# Radio.net
KiCad netlist of a schematic drawn in EAGLE
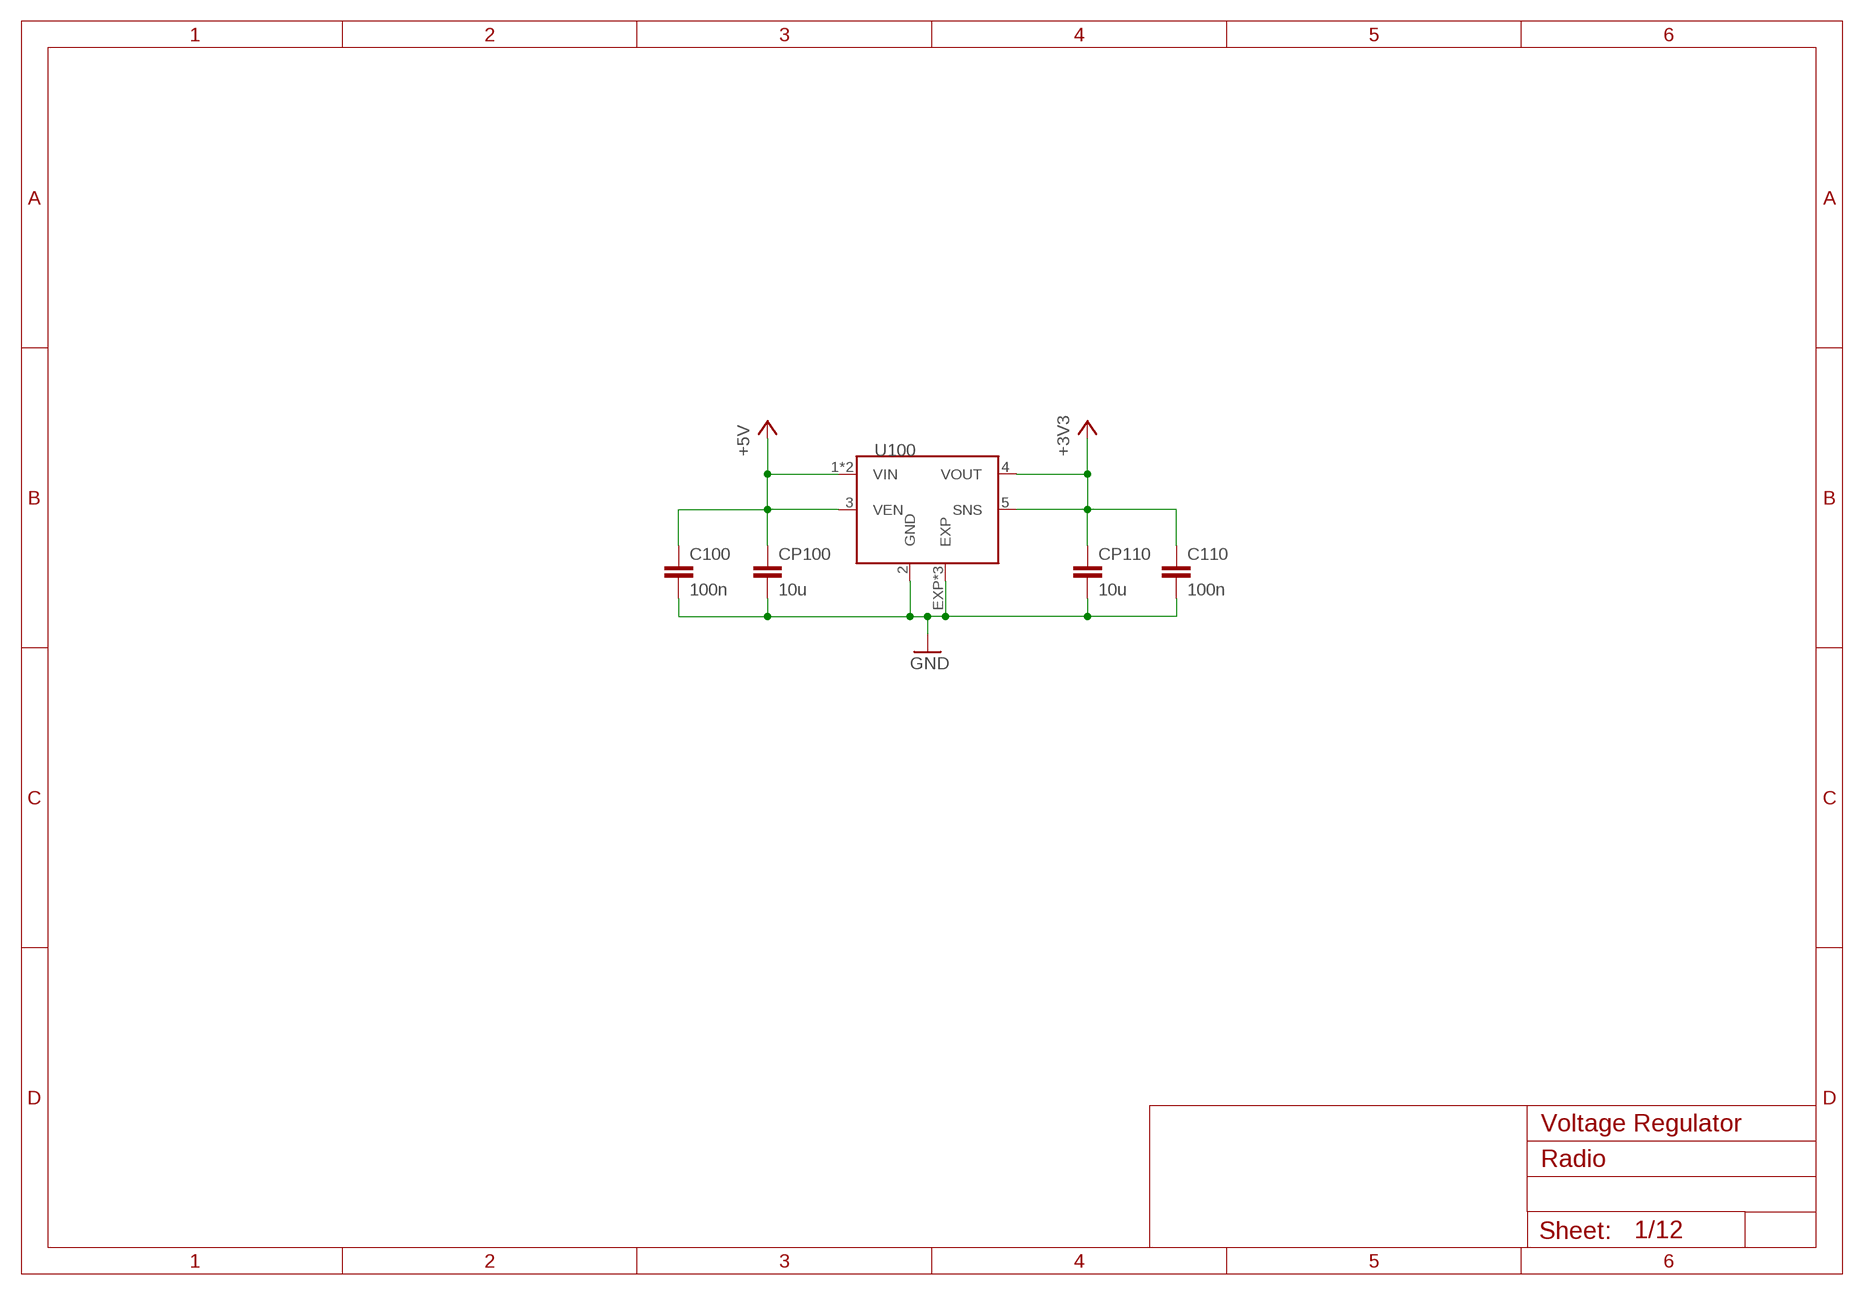
[diagram p0: schematic, sheet 1]
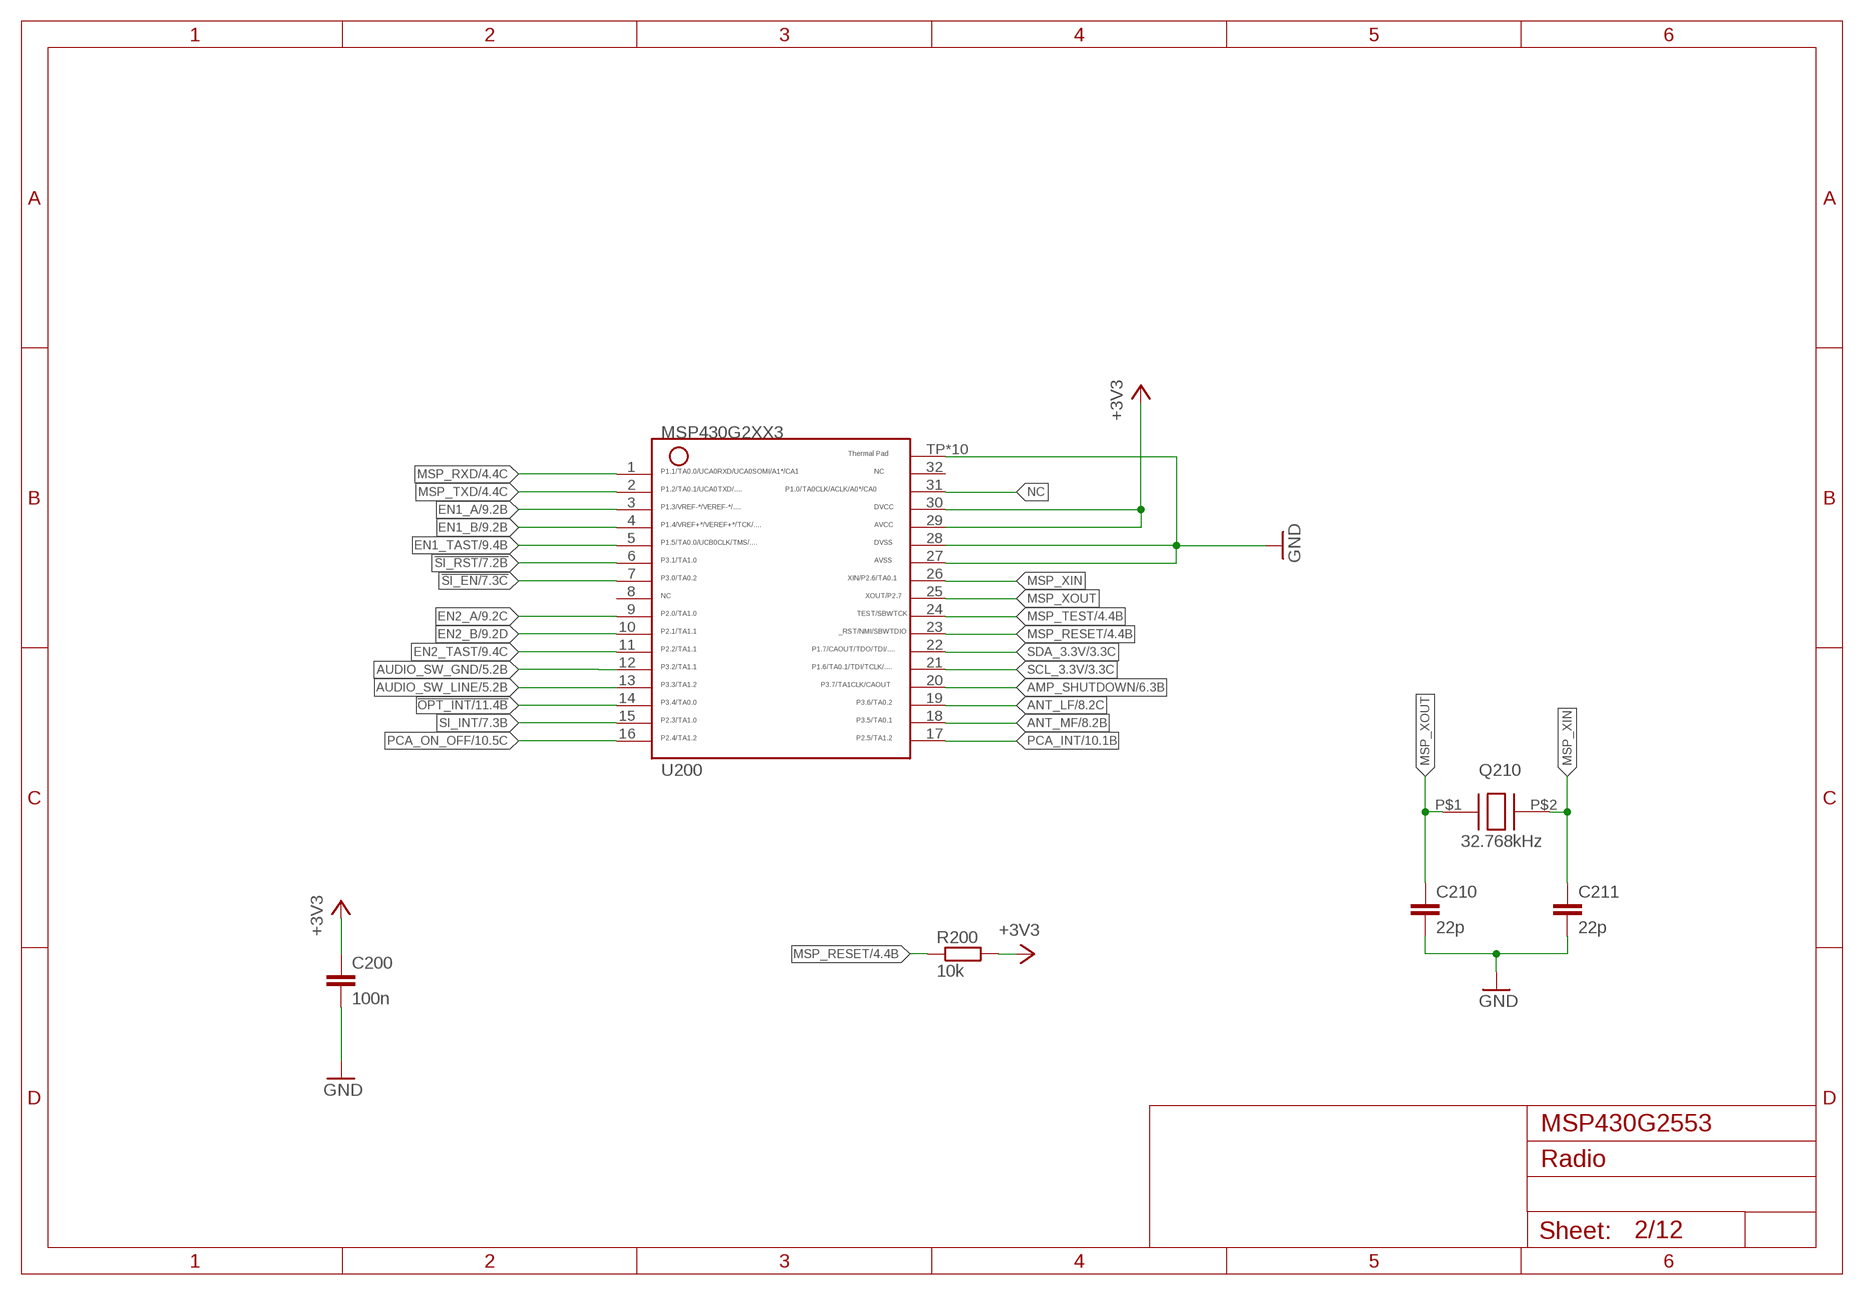
[diagram p1: schematic, sheet 2]
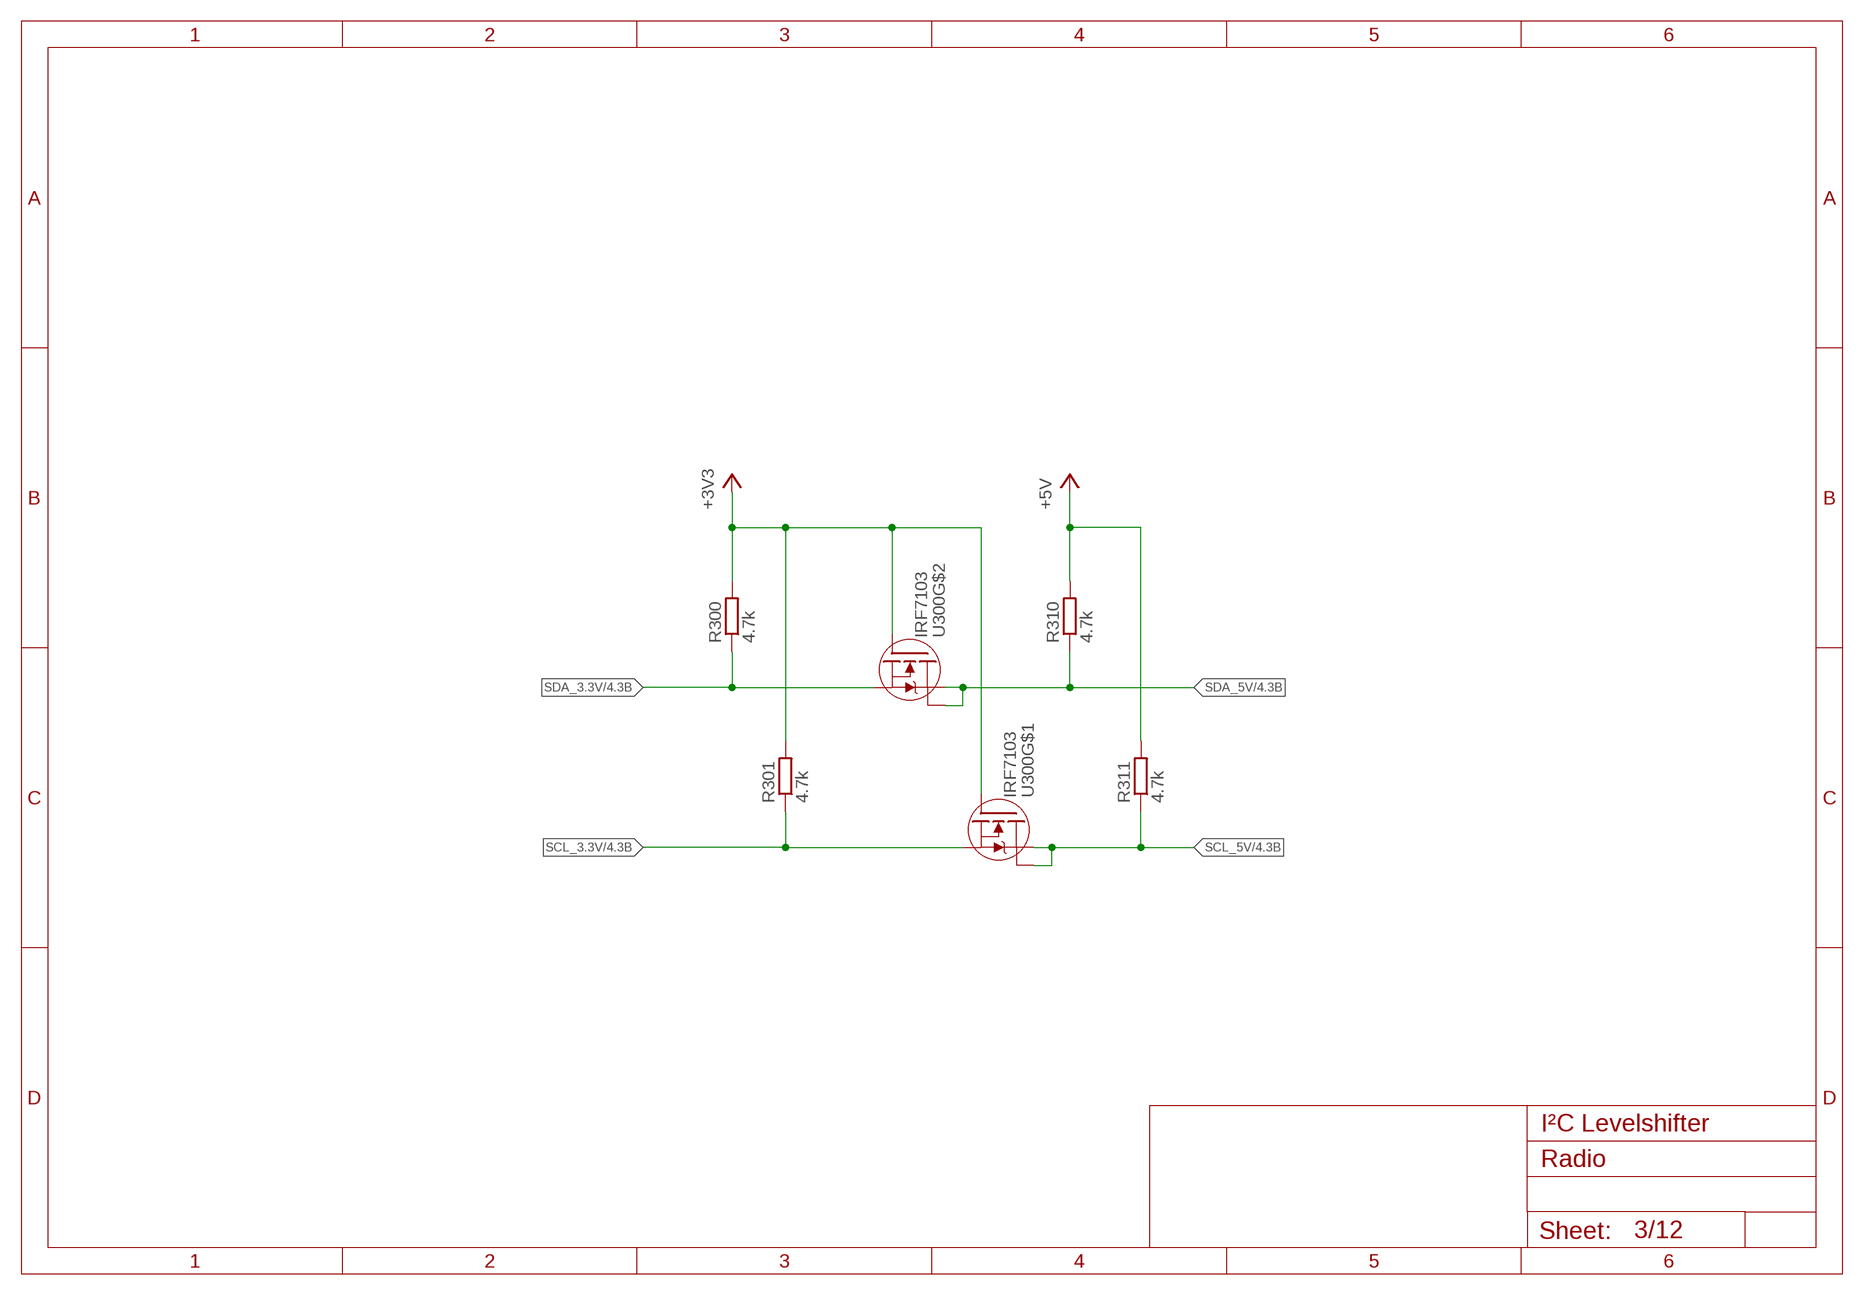
[diagram p2: schematic, sheet 3]
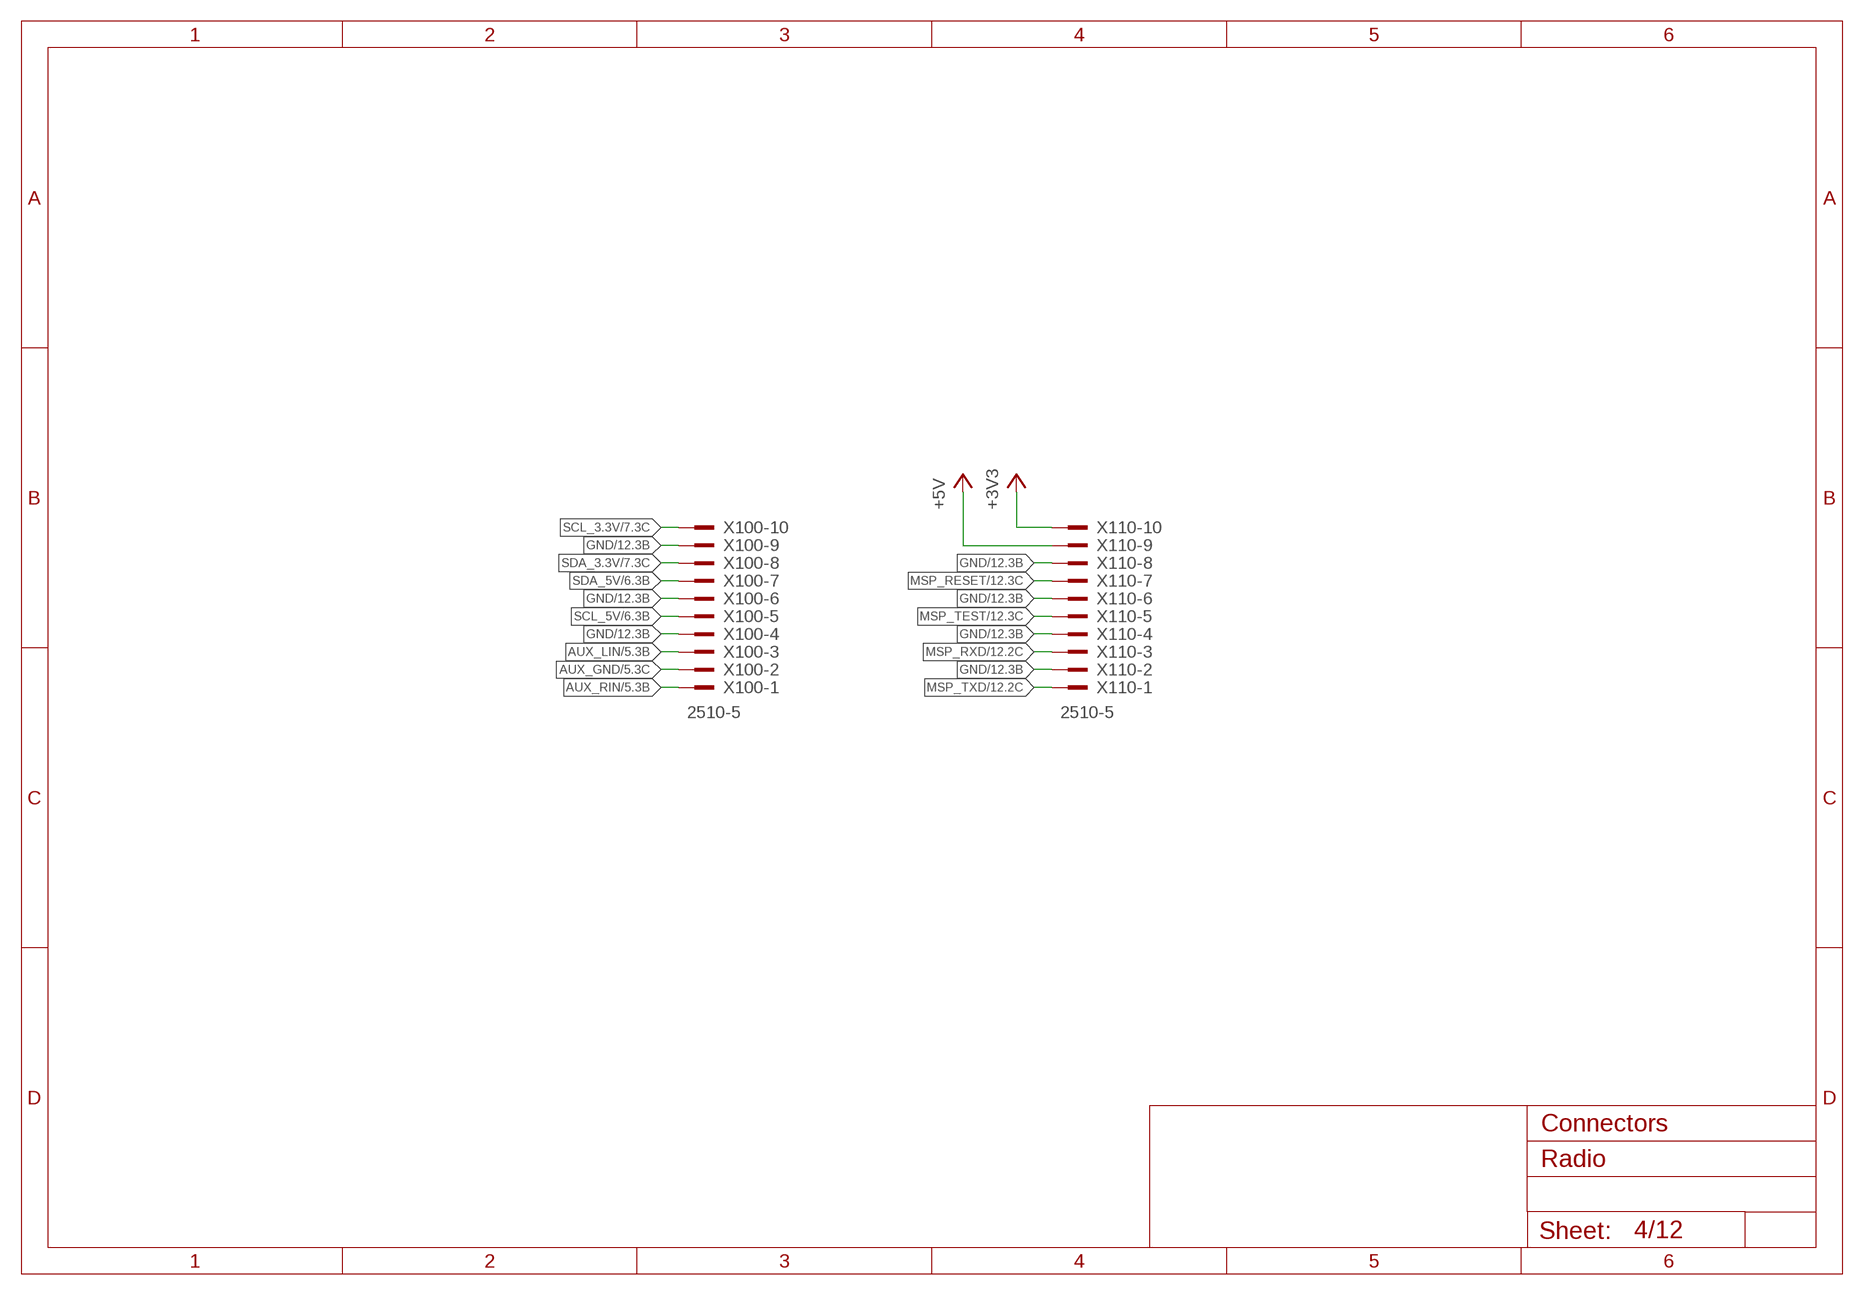
[diagram p3: schematic, sheet 4]
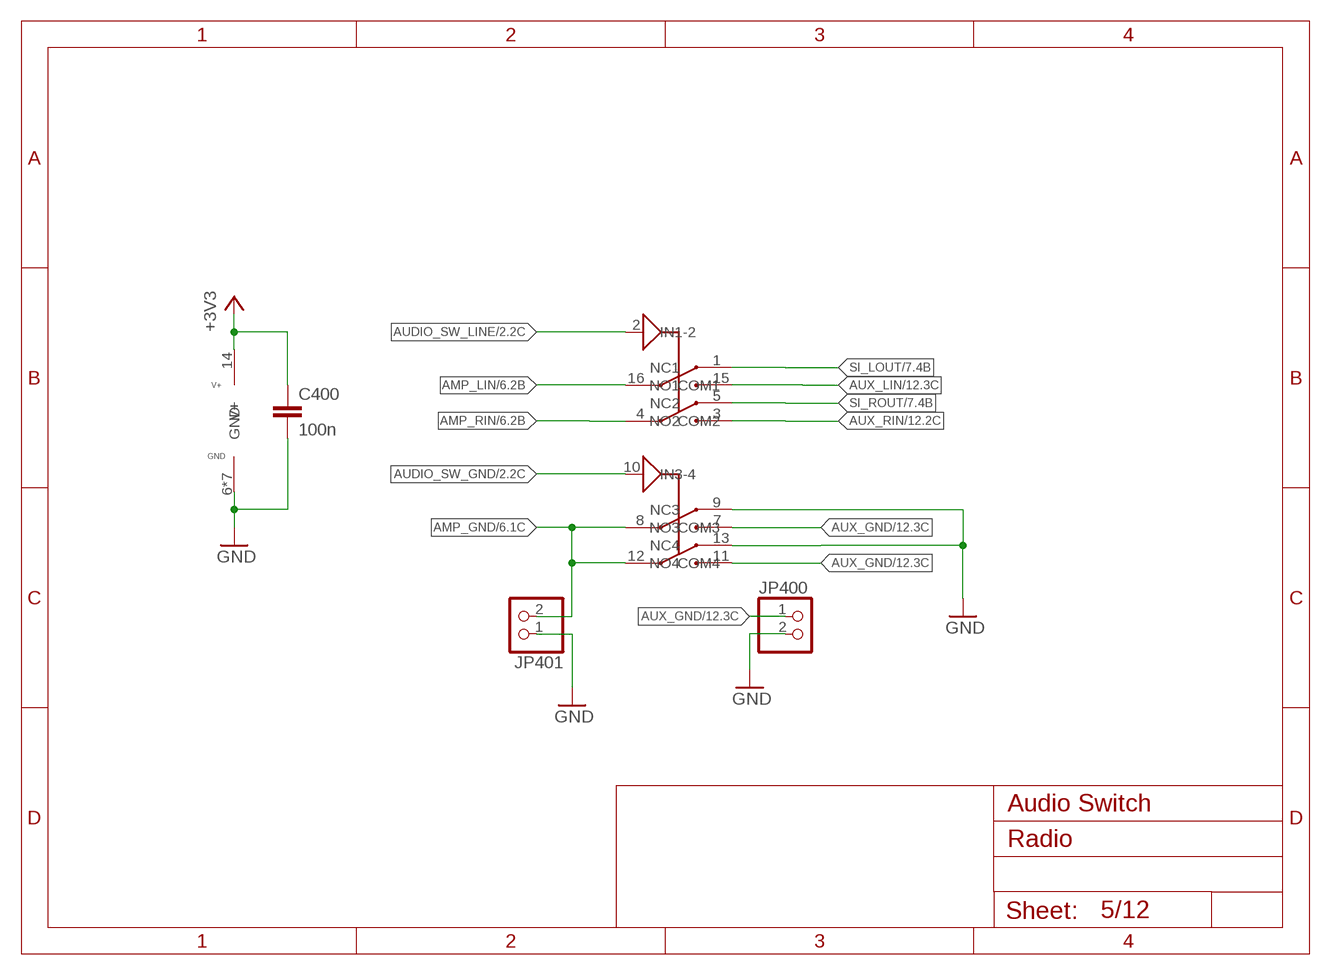
[diagram p4: schematic, sheet 5]
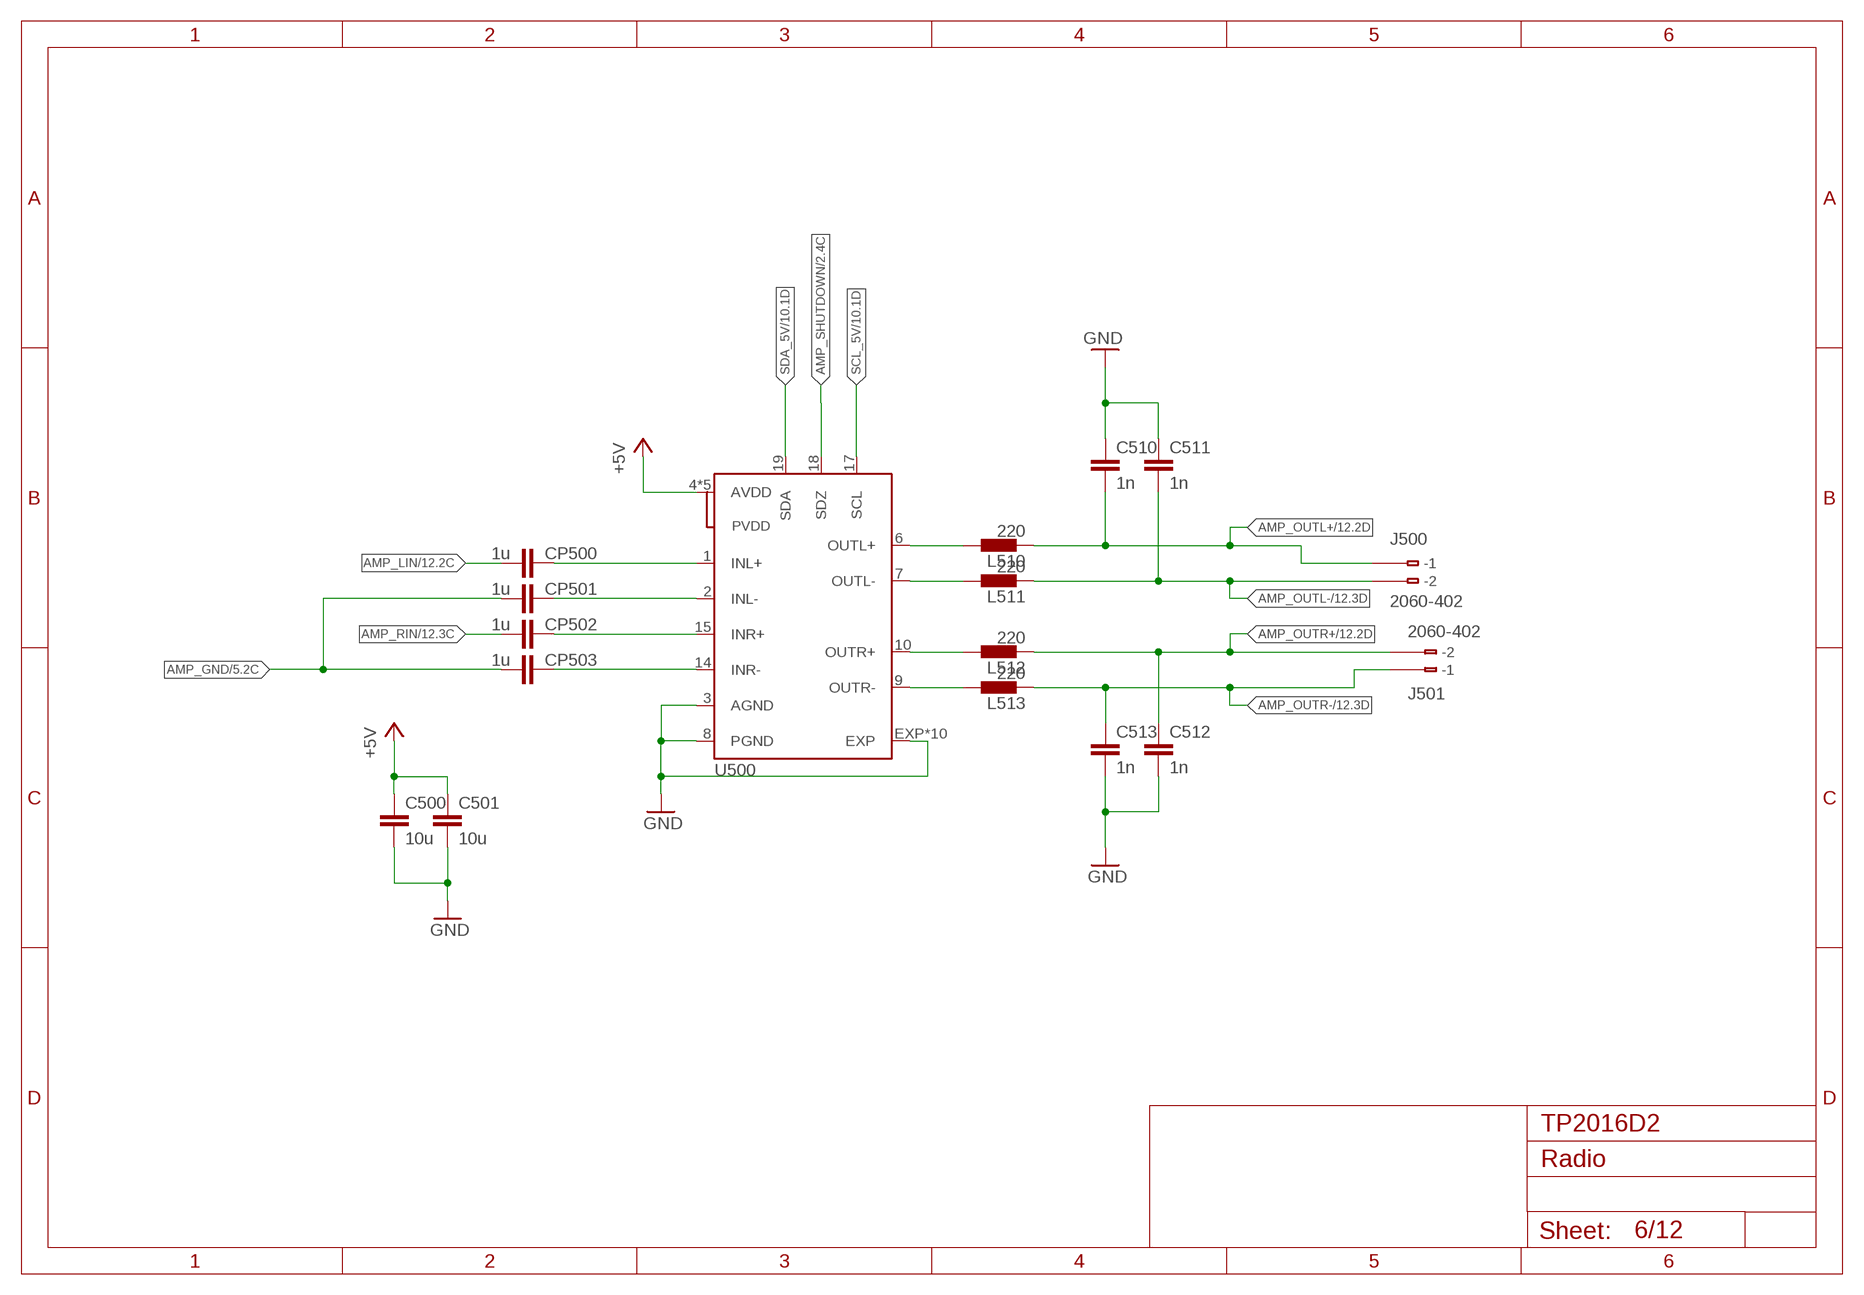
[diagram p5: schematic, sheet 6]
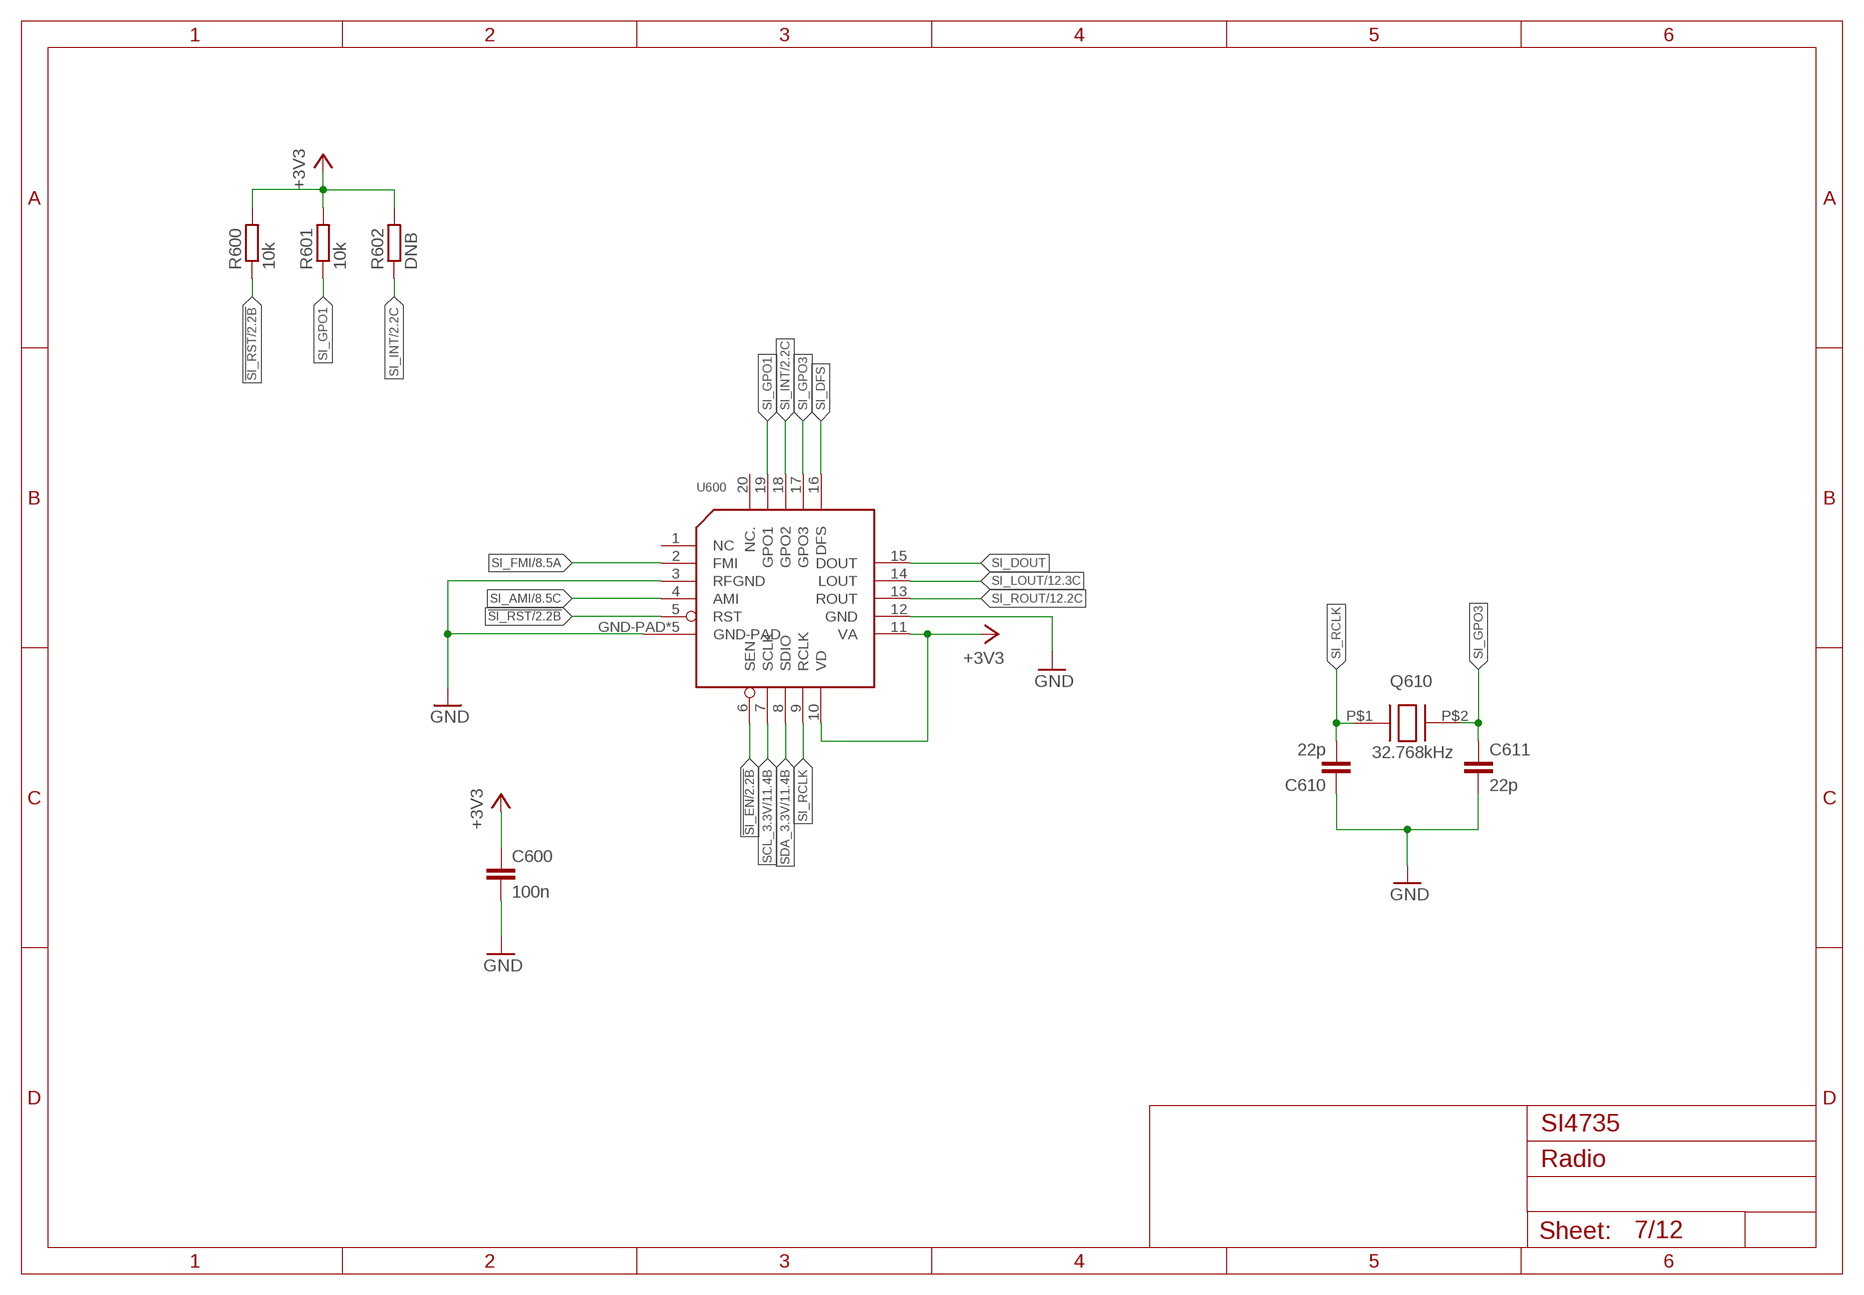
[diagram p6: schematic, sheet 7]
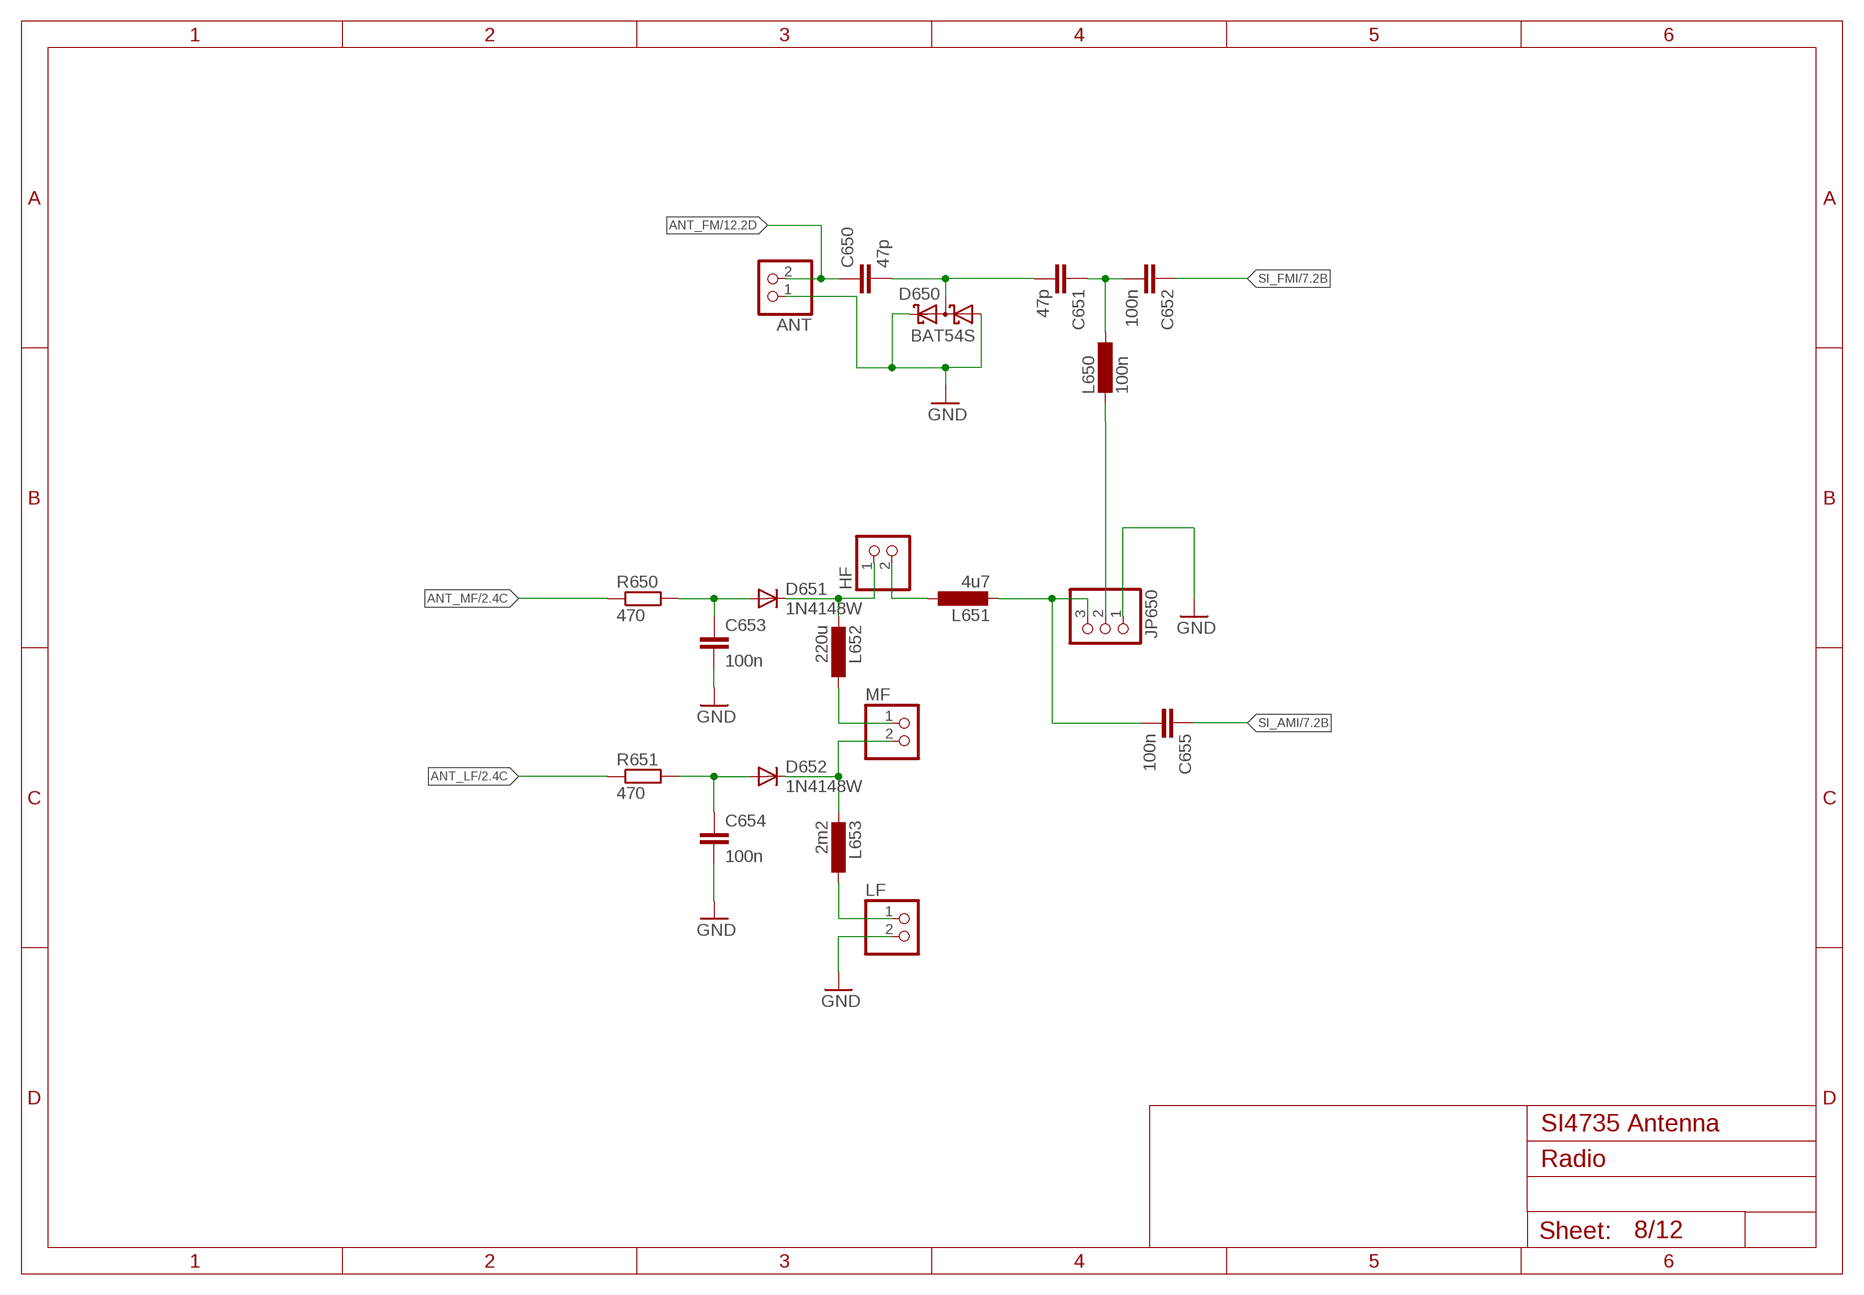
[diagram p7: schematic, sheet 8]
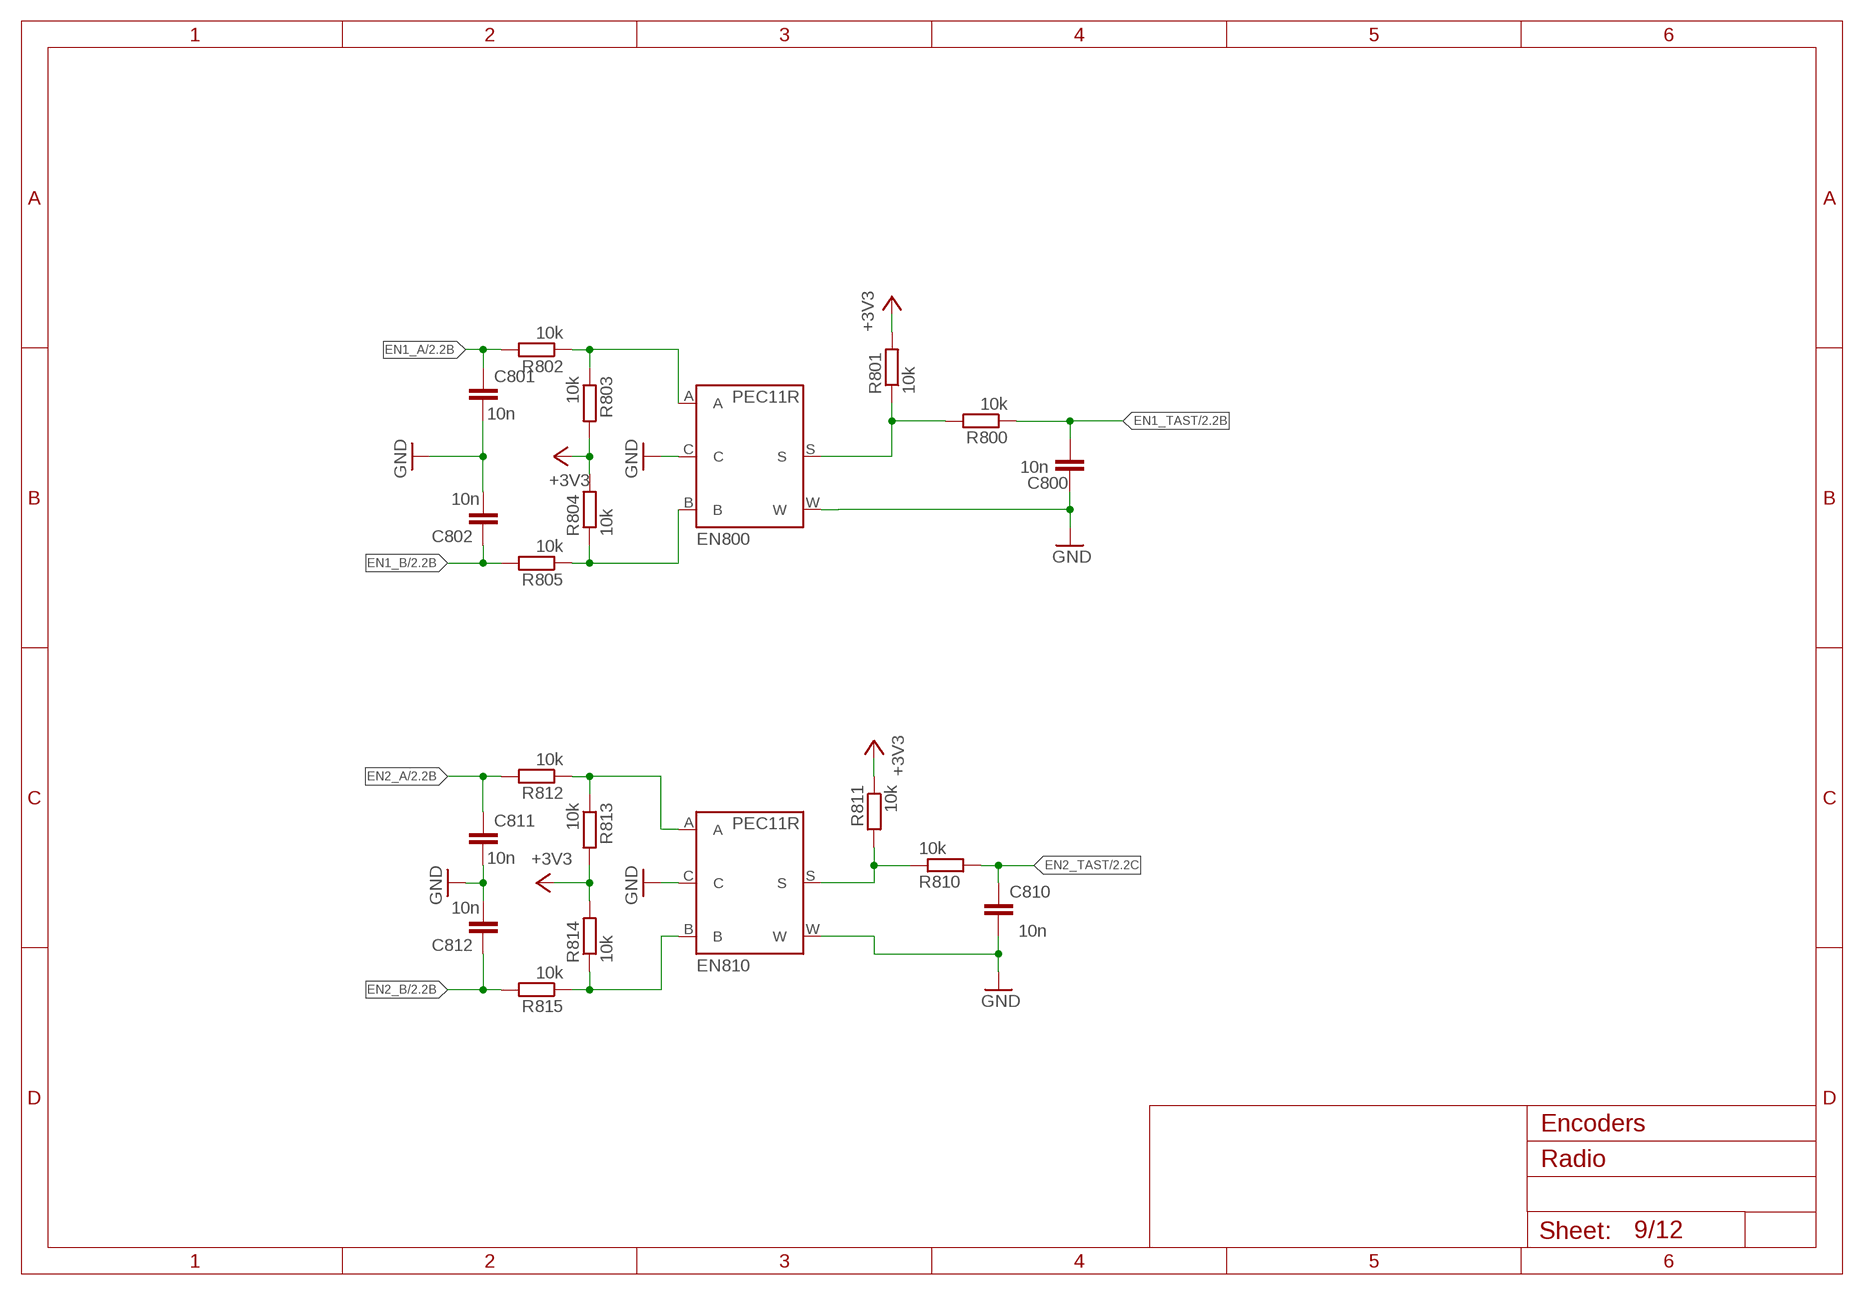
[diagram p8: schematic, sheet 9]
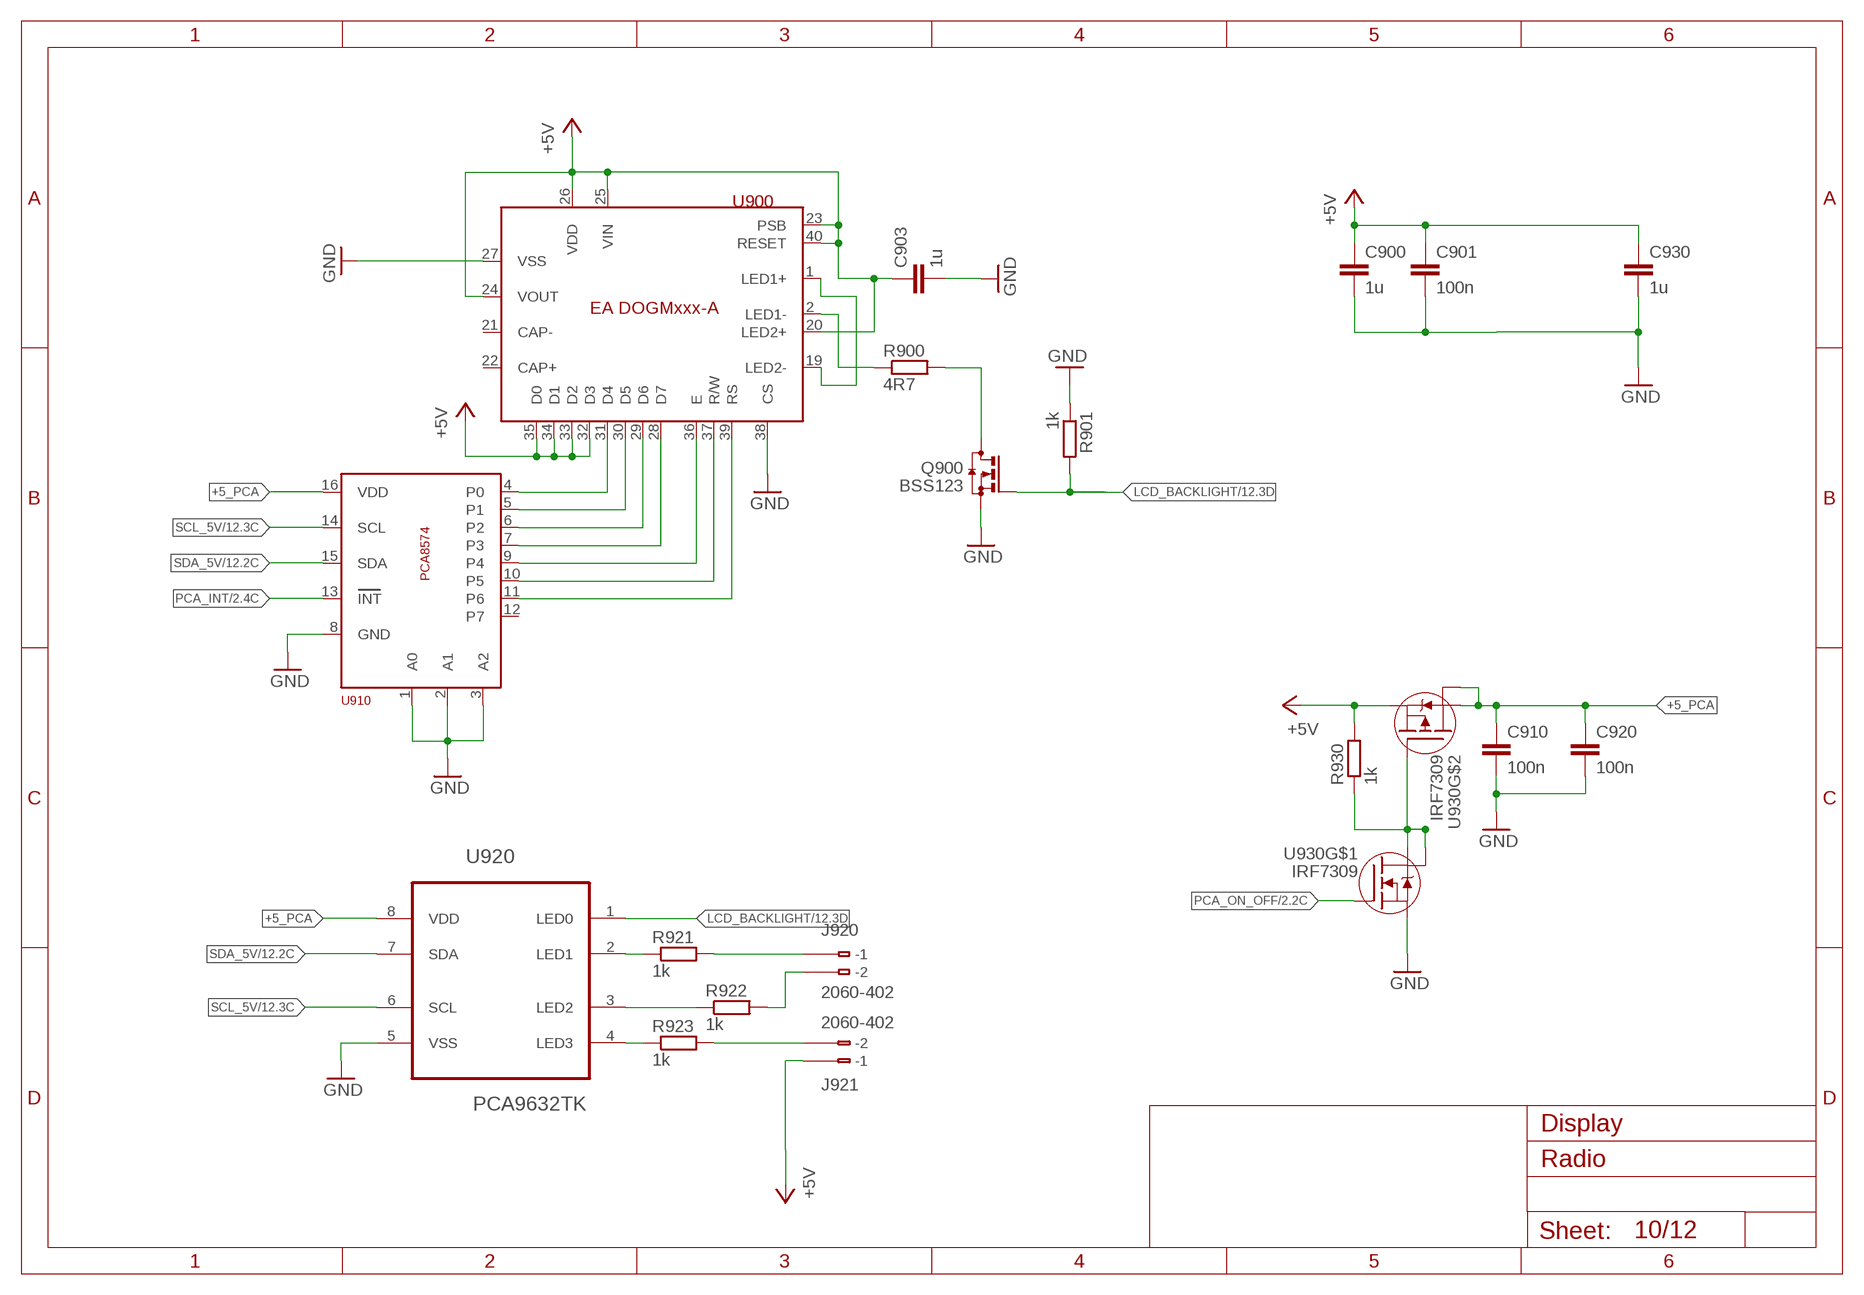
[diagram p9: schematic, sheet 10]
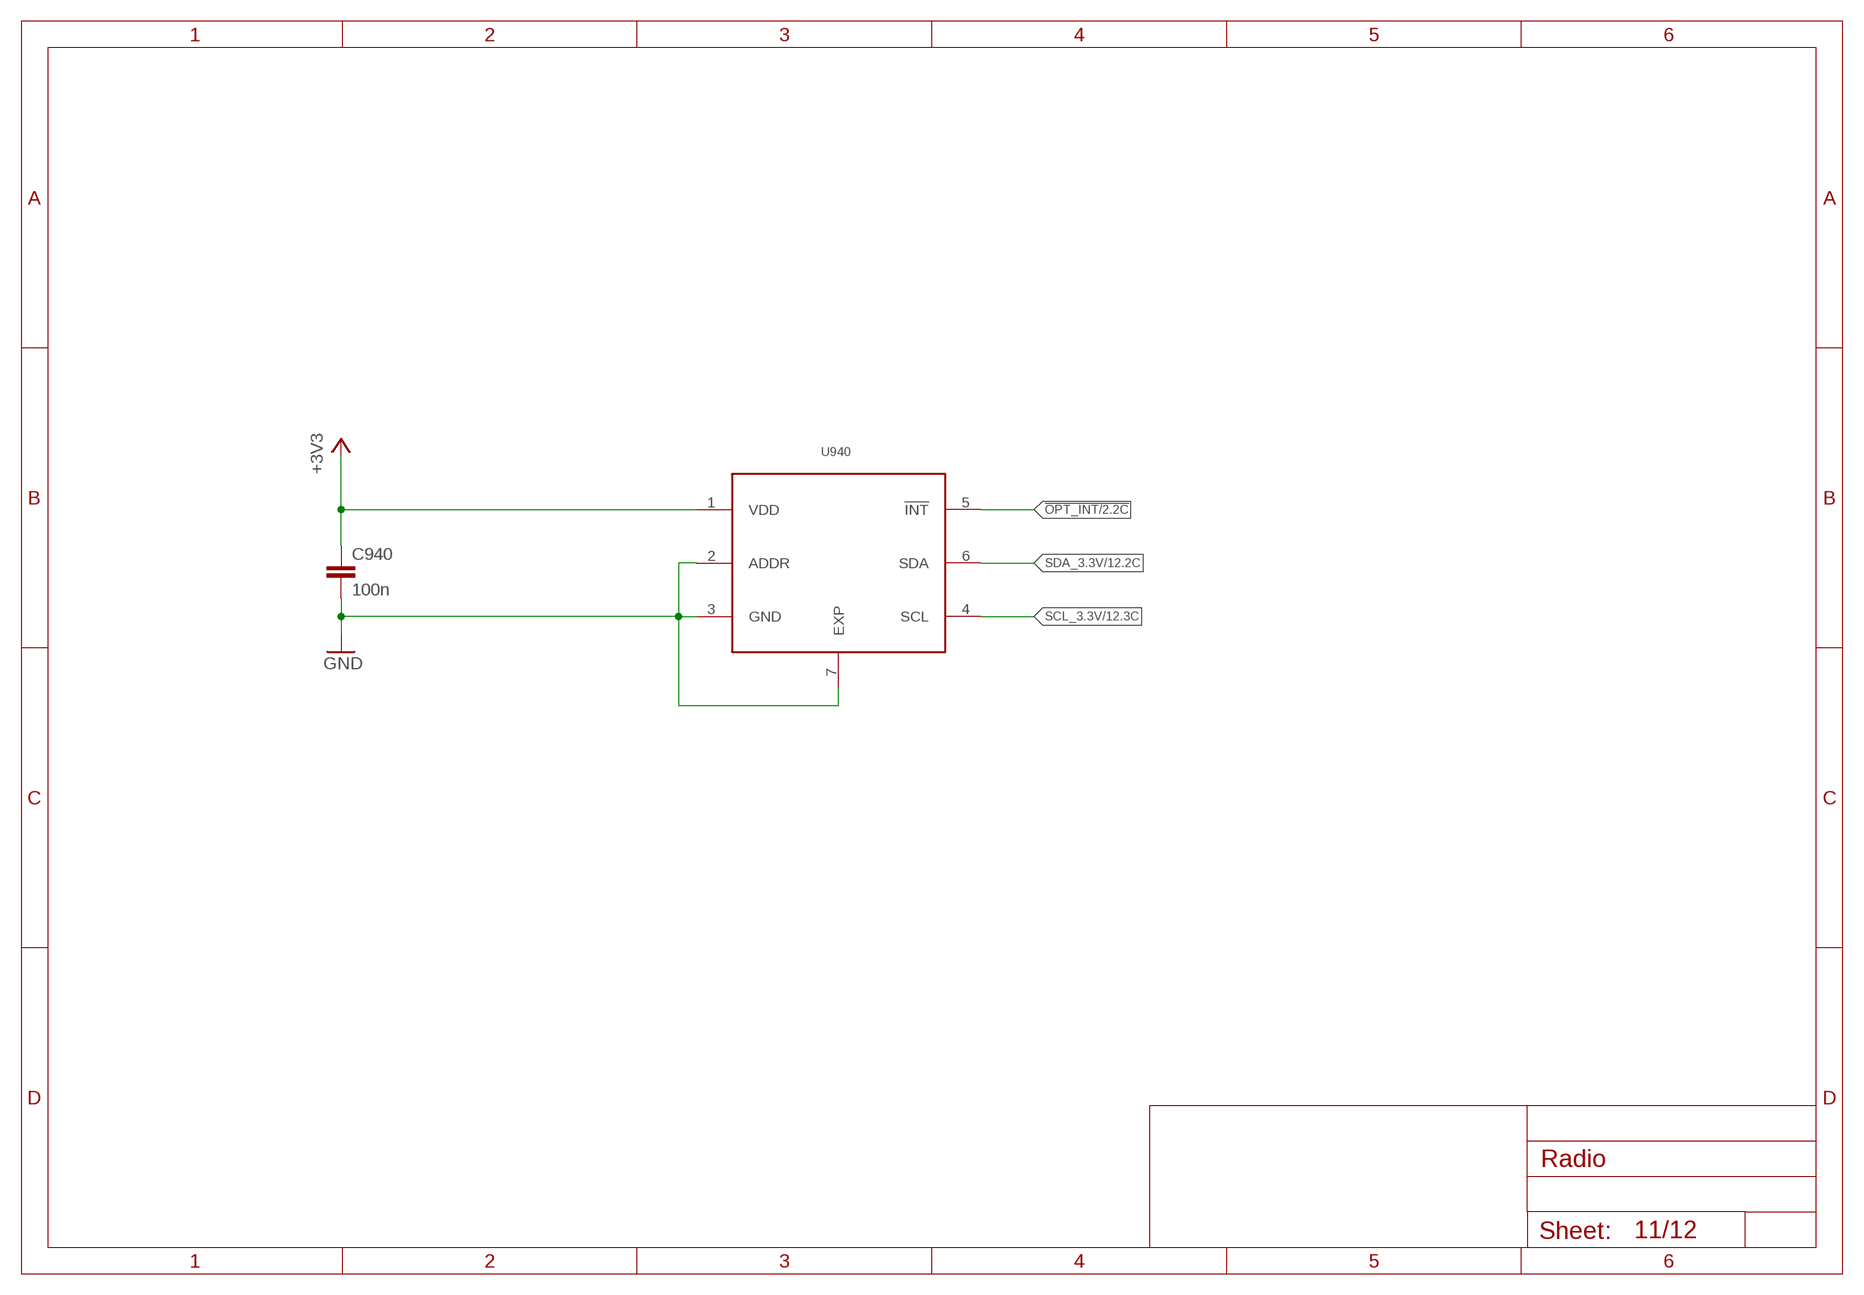
[diagram p10: schematic, sheet 11]
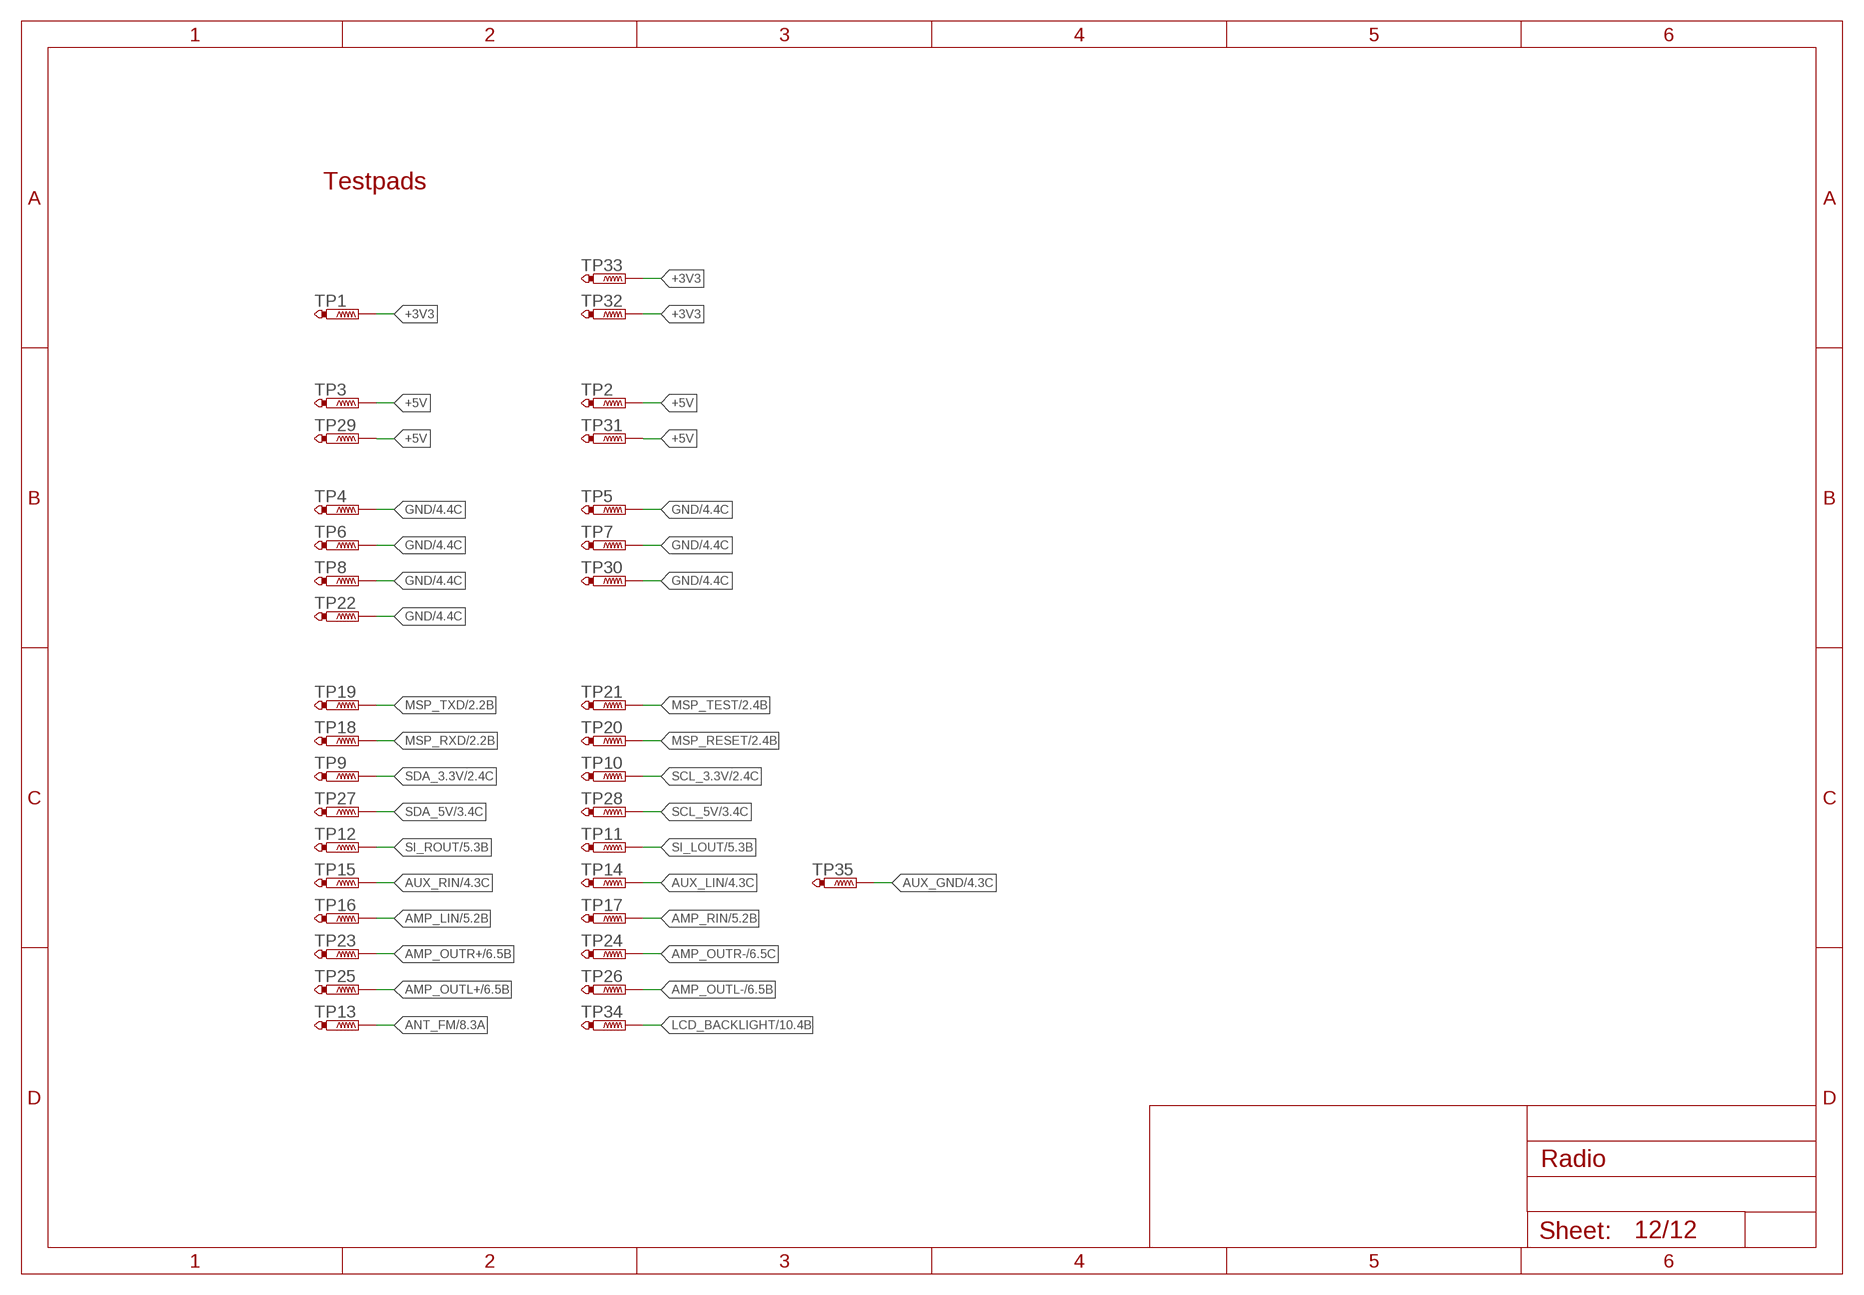
[diagram p11: schematic, sheet 12]

(export (version "E")
  (design (tool "Eeschema 10.0.6"))
  (components
    (comp (ref "TP1")
      (value "PTR1B1,27")
      (footprint "eagle-import:B1,27")
      (libsource (lib "eagle-import") (part "PTR1B1,27"))
    )
    (comp (ref "TP2")
      (value "PTR1B1,27")
      (footprint "eagle-import:B1,27")
      (libsource (lib "eagle-import") (part "PTR1B1,27"))
    )
    (comp (ref "TP3")
      (value "PTR1B1,27")
      (footprint "eagle-import:B1,27")
      (libsource (lib "eagle-import") (part "PTR1B1,27"))
    )
    (comp (ref "TP4")
      (value "PTR1B2,54")
      (footprint "eagle-import:B2,54")
      (libsource (lib "eagle-import") (part "PTR1B2,54"))
    )
    (comp (ref "TP5")
      (value "PTR1B2,54")
      (footprint "eagle-import:B2,54")
      (libsource (lib "eagle-import") (part "PTR1B2,54"))
    )
    (comp (ref "TP6")
      (value "PTR1B2,54")
      (footprint "eagle-import:B2,54")
      (libsource (lib "eagle-import") (part "PTR1B2,54"))
    )
    (comp (ref "TP7")
      (value "PTR1B2,54")
      (footprint "eagle-import:B2,54")
      (libsource (lib "eagle-import") (part "PTR1B2,54"))
    )
    (comp (ref "TP8")
      (value "PTR1B2,54")
      (footprint "eagle-import:B2,54")
      (libsource (lib "eagle-import") (part "PTR1B2,54"))
    )
    (comp (ref "TP9")
      (value "PTR1B1,27")
      (footprint "eagle-import:B1,27")
      (libsource (lib "eagle-import") (part "PTR1B1,27"))
    )
    (comp (ref "TP10")
      (value "PTR1B1,27")
      (footprint "eagle-import:B1,27")
      (libsource (lib "eagle-import") (part "PTR1B1,27"))
    )
    (comp (ref "TP11")
      (value "PTR1B1,27")
      (footprint "eagle-import:B1,27")
      (libsource (lib "eagle-import") (part "PTR1B1,27"))
    )
    (comp (ref "TP12")
      (value "PTR1B1,27")
      (footprint "eagle-import:B1,27")
      (libsource (lib "eagle-import") (part "PTR1B1,27"))
    )
    (comp (ref "TP13")
      (value "PTR1B1,27")
      (footprint "eagle-import:B1,27")
      (libsource (lib "eagle-import") (part "PTR1B1,27"))
    )
    (comp (ref "TP14")
      (value "PTR1B1,27")
      (footprint "eagle-import:B1,27")
      (libsource (lib "eagle-import") (part "PTR1B1,27"))
    )
    (comp (ref "TP15")
      (value "PTR1B1,27")
      (footprint "eagle-import:B1,27")
      (libsource (lib "eagle-import") (part "PTR1B1,27"))
    )
    (comp (ref "TP16")
      (value "PTR1B1,27")
      (footprint "eagle-import:B1,27")
      (libsource (lib "eagle-import") (part "PTR1B1,27"))
    )
    (comp (ref "TP17")
      (value "PTR1B1,27")
      (footprint "eagle-import:B1,27")
      (libsource (lib "eagle-import") (part "PTR1B1,27"))
    )
    (comp (ref "TP18")
      (value "PTR1B1,27")
      (footprint "eagle-import:B1,27")
      (libsource (lib "eagle-import") (part "PTR1B1,27"))
    )
    (comp (ref "TP19")
      (value "PTR1B1,27")
      (footprint "eagle-import:B1,27")
      (libsource (lib "eagle-import") (part "PTR1B1,27"))
    )
    (comp (ref "TP20")
      (value "PTR1B1,27")
      (footprint "eagle-import:B1,27")
      (libsource (lib "eagle-import") (part "PTR1B1,27"))
    )
    (comp (ref "TP21")
      (value "PTR1B1,27")
      (footprint "eagle-import:B1,27")
      (libsource (lib "eagle-import") (part "PTR1B1,27"))
    )
    (comp (ref "TP22")
      (value "PTR1B2,54")
      (footprint "eagle-import:B2,54")
      (libsource (lib "eagle-import") (part "PTR1B2,54"))
    )
    (comp (ref "TP23")
      (value "PTR1B2,54")
      (footprint "eagle-import:B2,54")
      (libsource (lib "eagle-import") (part "PTR1B2,54"))
    )
    (comp (ref "TP24")
      (value "PTR1B2,54")
      (footprint "eagle-import:B2,54")
      (libsource (lib "eagle-import") (part "PTR1B2,54"))
    )
    (comp (ref "TP25")
      (value "PTR1B2,54")
      (footprint "eagle-import:B2,54")
      (libsource (lib "eagle-import") (part "PTR1B2,54"))
    )
    (comp (ref "TP26")
      (value "PTR1B2,54")
      (footprint "eagle-import:B2,54")
      (libsource (lib "eagle-import") (part "PTR1B2,54"))
    )
    (comp (ref "TP27")
      (value "PTR1B1,27")
      (footprint "eagle-import:B1,27")
      (libsource (lib "eagle-import") (part "PTR1B1,27"))
    )
    (comp (ref "TP28")
      (value "PTR1B1,27")
      (footprint "eagle-import:B1,27")
      (libsource (lib "eagle-import") (part "PTR1B1,27"))
    )
    (comp (ref "TP29")
      (value "PTR1B2,54")
      (footprint "eagle-import:B2,54")
      (libsource (lib "eagle-import") (part "PTR1B2,54"))
    )
    (comp (ref "TP30")
      (value "PTR1B2,54")
      (footprint "eagle-import:B2,54")
      (libsource (lib "eagle-import") (part "PTR1B2,54"))
    )
    (comp (ref "TP31")
      (value "PTR1B2,54")
      (footprint "eagle-import:B2,54")
      (libsource (lib "eagle-import") (part "PTR1B2,54"))
    )
    (comp (ref "TP32")
      (value "PTR1B1,27")
      (footprint "eagle-import:B1,27")
      (libsource (lib "eagle-import") (part "PTR1B1,27"))
    )
    (comp (ref "TP33")
      (value "PTR1B1,27")
      (footprint "eagle-import:B1,27")
      (libsource (lib "eagle-import") (part "PTR1B1,27"))
    )
    (comp (ref "TP34")
      (value "PTR1B1,27")
      (footprint "eagle-import:B1,27")
      (libsource (lib "eagle-import") (part "PTR1B1,27"))
    )
    (comp (ref "TP35")
      (value "PTR1B1,27")
      (footprint "eagle-import:B1,27")
      (libsource (lib "eagle-import") (part "PTR1B1,27"))
    )
    (comp (ref "C100")
      (value "100n")
      (footprint "eagle-import:C1206K")
      (libsource (lib "eagle-import") (part "C-EUC1206K"))
    )
    (comp (ref "C110")
      (value "100n")
      (footprint "eagle-import:C1206K")
      (libsource (lib "eagle-import") (part "C-EUC1206K"))
    )
    (comp (ref "CP100")
      (value "10u")
      (footprint "eagle-import:C1206K")
      (libsource (lib "eagle-import") (part "C-EUC1206K"))
    )
    (comp (ref "CP110")
      (value "10u")
      (footprint "eagle-import:C1206K")
      (libsource (lib "eagle-import") (part "C-EUC1206K"))
    )
    (comp (ref "U100")
      (value "LP38693")
      (footprint "eagle-import:LP38693_WSON")
      (libsource (lib "eagle-import") (part "LP38693"))
    )
    (comp (ref "ANT")
      (value "PINHD-1X2")
      (footprint "eagle-import:1X02")
      (libsource (lib "eagle-import") (part "PINHD-1X2"))
    )
    (comp (ref "C650")
      (value "47p")
      (footprint "eagle-import:C1206K")
      (libsource (lib "eagle-import") (part "C-EUC1206K"))
    )
    (comp (ref "C651")
      (value "47p")
      (footprint "eagle-import:C1206K")
      (libsource (lib "eagle-import") (part "C-EUC1206K"))
    )
    (comp (ref "C652")
      (value "100n")
      (footprint "eagle-import:C1206K")
      (libsource (lib "eagle-import") (part "C-EUC1206K"))
    )
    (comp (ref "C653")
      (value "100n")
      (footprint "eagle-import:C1206K")
      (libsource (lib "eagle-import") (part "C-EUC1206K"))
    )
    (comp (ref "C654")
      (value "100n")
      (footprint "eagle-import:C1206K")
      (libsource (lib "eagle-import") (part "C-EUC1206K"))
    )
    (comp (ref "C655")
      (value "100n")
      (footprint "eagle-import:C1206K")
      (libsource (lib "eagle-import") (part "C-EUC1206K"))
    )
    (comp (ref "D650")
      (value "BAT54S")
      (footprint "eagle-import:SOT23")
      (libsource (lib "eagle-import") (part "BAT54S"))
    )
    (comp (ref "D651")
      (value "1N4148W")
      (footprint "eagle-import:SOD123")
      (libsource (lib "eagle-import") (part "DIODE-SOD123"))
    )
    (comp (ref "D652")
      (value "1N4148W")
      (footprint "eagle-import:SOD123")
      (libsource (lib "eagle-import") (part "DIODE-SOD123"))
    )
    (comp (ref "HF")
      (value "PINHD-1X2")
      (footprint "eagle-import:1X02")
      (libsource (lib "eagle-import") (part "PINHD-1X2"))
    )
    (comp (ref "JP650")
      (value "PINHD-1X3")
      (footprint "eagle-import:1X03")
      (libsource (lib "eagle-import") (part "PINHD-1X3"))
    )
    (comp (ref "L650")
      (value "100n")
      (footprint "eagle-import:L1210")
      (libsource (lib "eagle-import") (part "L-EU"))
    )
    (comp (ref "L651")
      (value "4u7")
      (footprint "eagle-import:L1210")
      (libsource (lib "eagle-import") (part "L-EU"))
    )
    (comp (ref "L652")
      (value "220u")
      (footprint "eagle-import:L1210")
      (libsource (lib "eagle-import") (part "L-EU"))
    )
    (comp (ref "L653")
      (value "2m2")
      (footprint "eagle-import:L1812")
      (libsource (lib "eagle-import") (part "L-EUL1812"))
    )
    (comp (ref "LF")
      (value "PINHD-1X2")
      (footprint "eagle-import:1X02")
      (libsource (lib "eagle-import") (part "PINHD-1X2"))
    )
    (comp (ref "MF")
      (value "PINHD-1X2")
      (footprint "eagle-import:1X02")
      (libsource (lib "eagle-import") (part "PINHD-1X2"))
    )
    (comp (ref "R650")
      (value "470")
      (footprint "eagle-import:R1206")
      (libsource (lib "eagle-import") (part "R-EU_R1206"))
    )
    (comp (ref "R651")
      (value "470")
      (footprint "eagle-import:R1206")
      (libsource (lib "eagle-import") (part "R-EU_R1206"))
    )
    (comp (ref "C400")
      (value "100n")
      (footprint "eagle-import:C1206K")
      (libsource (lib "eagle-import") (part "C-EUC1206K"))
    )
    (comp (ref "JP400")
      (value "PINHD-1X2")
      (footprint "eagle-import:1X02")
      (libsource (lib "eagle-import") (part "PINHD-1X2"))
    )
    (comp (ref "JP401")
      (value "PINHD-1X2")
      (footprint "eagle-import:1X02")
      (libsource (lib "eagle-import") (part "PINHD-1X2"))
    )
    (comp (ref "U400")
      (value "TS3A44159RGT")
      (footprint "eagle-import:QFN16")
      (libsource (lib "eagle-import") (part "TS3A44159RGT"))
    )
    (comp (ref "C800")
      (value "10n")
      (footprint "eagle-import:C1206K")
      (libsource (lib "eagle-import") (part "C-EUC1206K"))
    )
    (comp (ref "C801")
      (value "10n")
      (footprint "eagle-import:C1206K")
      (libsource (lib "eagle-import") (part "C-EUC1206K"))
    )
    (comp (ref "C802")
      (value "10n")
      (footprint "eagle-import:C1206K")
      (libsource (lib "eagle-import") (part "C-EUC1206K"))
    )
    (comp (ref "C810")
      (value "10n")
      (footprint "eagle-import:C1206K")
      (libsource (lib "eagle-import") (part "C-EUC1206K"))
    )
    (comp (ref "C811")
      (value "10n")
      (footprint "eagle-import:C1206K")
      (libsource (lib "eagle-import") (part "C-EUC1206K"))
    )
    (comp (ref "C812")
      (value "10n")
      (footprint "eagle-import:C1206K")
      (libsource (lib "eagle-import") (part "C-EUC1206K"))
    )
    (comp (ref "EN800")
      (value "PEC11R")
      (footprint "eagle-import:PEC11R")
      (libsource (lib "eagle-import") (part "PEC11R"))
    )
    (comp (ref "EN810")
      (value "PEC11R")
      (footprint "eagle-import:PEC11R")
      (libsource (lib "eagle-import") (part "PEC11R"))
    )
    (comp (ref "R800")
      (value "10k")
      (footprint "eagle-import:R1206")
      (libsource (lib "eagle-import") (part "R-EU_R1206"))
    )
    (comp (ref "R801")
      (value "10k")
      (footprint "eagle-import:R1206")
      (libsource (lib "eagle-import") (part "R-EU_R1206"))
    )
    (comp (ref "R802")
      (value "10k")
      (footprint "eagle-import:R1206")
      (libsource (lib "eagle-import") (part "R-EU_R1206"))
    )
    (comp (ref "R803")
      (value "10k")
      (footprint "eagle-import:R1206")
      (libsource (lib "eagle-import") (part "R-EU_R1206"))
    )
    (comp (ref "R804")
      (value "10k")
      (footprint "eagle-import:R1206")
      (libsource (lib "eagle-import") (part "R-EU_R1206"))
    )
    (comp (ref "R805")
      (value "10k")
      (footprint "eagle-import:R1206")
      (libsource (lib "eagle-import") (part "R-EU_R1206"))
    )
    (comp (ref "R810")
      (value "10k")
      (footprint "eagle-import:R1206")
      (libsource (lib "eagle-import") (part "R-EU_R1206"))
    )
    (comp (ref "R811")
      (value "10k")
      (footprint "eagle-import:R1206")
      (libsource (lib "eagle-import") (part "R-EU_R1206"))
    )
    (comp (ref "R812")
      (value "10k")
      (footprint "eagle-import:R1206")
      (libsource (lib "eagle-import") (part "R-EU_R1206"))
    )
    (comp (ref "R813")
      (value "10k")
      (footprint "eagle-import:R1206")
      (libsource (lib "eagle-import") (part "R-EU_R1206"))
    )
    (comp (ref "R814")
      (value "10k")
      (footprint "eagle-import:R1206")
      (libsource (lib "eagle-import") (part "R-EU_R1206"))
    )
    (comp (ref "R815")
      (value "10k")
      (footprint "eagle-import:R1206")
      (libsource (lib "eagle-import") (part "R-EU_R1206"))
    )
    (comp (ref "C200")
      (value "100n")
      (footprint "eagle-import:C1206K")
      (libsource (lib "eagle-import") (part "C-EUC1206K"))
    )
    (comp (ref "C210")
      (value "22p")
      (footprint "eagle-import:C1206K")
      (libsource (lib "eagle-import") (part "C-EUC1206K"))
    )
    (comp (ref "C211")
      (value "22p")
      (footprint "eagle-import:C1206K")
      (libsource (lib "eagle-import") (part "C-EUC1206K"))
    )
    (comp (ref "Q210")
      (value "32.768kHz")
      (footprint "eagle-import:CM7V-T1A")
      (libsource (lib "eagle-import") (part "QUARZ32.768KHZSMD"))
    )
    (comp (ref "R200")
      (value "10k")
      (footprint "eagle-import:R1206")
      (libsource (lib "eagle-import") (part "R-EU_R1206"))
    )
    (comp (ref "U200")
      (value "MSP430G2553")
      (footprint "eagle-import:RHB32")
      (libsource (lib "eagle-import") (part "G2XX3---RHB32"))
    )
    (comp (ref "C500")
      (value "10u")
      (footprint "eagle-import:C1206K")
      (libsource (lib "eagle-import") (part "C-EUC1206K"))
    )
    (comp (ref "C501")
      (value "10u")
      (footprint "eagle-import:C1206K")
      (libsource (lib "eagle-import") (part "C-EUC1206K"))
    )
    (comp (ref "C510")
      (value "1n")
      (footprint "eagle-import:C1206K")
      (libsource (lib "eagle-import") (part "C-EUC1206K"))
    )
    (comp (ref "C511")
      (value "1n")
      (footprint "eagle-import:C1206K")
      (libsource (lib "eagle-import") (part "C-EUC1206K"))
    )
    (comp (ref "C512")
      (value "1n")
      (footprint "eagle-import:C1206K")
      (libsource (lib "eagle-import") (part "C-EUC1206K"))
    )
    (comp (ref "C513")
      (value "1n")
      (footprint "eagle-import:C1206K")
      (libsource (lib "eagle-import") (part "C-EUC1206K"))
    )
    (comp (ref "CP500")
      (value "1u")
      (footprint "eagle-import:C1206K")
      (libsource (lib "eagle-import") (part "C-EUC1206K"))
    )
    (comp (ref "CP501")
      (value "1u")
      (footprint "eagle-import:C1206K")
      (libsource (lib "eagle-import") (part "C-EUC1206K"))
    )
    (comp (ref "CP502")
      (value "1u")
      (footprint "eagle-import:C1206K")
      (libsource (lib "eagle-import") (part "C-EUC1206K"))
    )
    (comp (ref "CP503")
      (value "1u")
      (footprint "eagle-import:C1206K")
      (libsource (lib "eagle-import") (part "C-EUC1206K"))
    )
    (comp (ref "J500")
      (value "2060-402")
      (footprint "eagle-import:WAGO_2060-402")
      (fields (field (name "MPN") "2060-402/998-404"))
      (libsource (lib "eagle-import") (part "2060-402"))
    )
    (comp (ref "J501")
      (value "2060-402")
      (footprint "eagle-import:WAGO_2060-402")
      (fields (field (name "MPN") "2060-402/998-404"))
      (libsource (lib "eagle-import") (part "2060-402"))
    )
    (comp (ref "L510")
      (value "220")
      (footprint "eagle-import:R0603")
      (libsource (lib "eagle-import") (part "BLM15H"))
    )
    (comp (ref "L511")
      (value "220")
      (footprint "eagle-import:R0603")
      (libsource (lib "eagle-import") (part "BLM15H"))
    )
    (comp (ref "L512")
      (value "220")
      (footprint "eagle-import:R0603")
      (libsource (lib "eagle-import") (part "BLM15H"))
    )
    (comp (ref "L513")
      (value "220")
      (footprint "eagle-import:R0603")
      (libsource (lib "eagle-import") (part "BLM15H"))
    )
    (comp (ref "U500")
      (value "TPA2016D2")
      (footprint "eagle-import:TPA2016D2_PWQFN-20")
      (libsource (lib "eagle-import") (part "TPA2016D2"))
    )
    (comp (ref "R300")
      (value "4.7k")
      (footprint "eagle-import:R1206")
      (libsource (lib "eagle-import") (part "R-EU_R1206"))
    )
    (comp (ref "R301")
      (value "4.7k")
      (footprint "eagle-import:R1206")
      (libsource (lib "eagle-import") (part "R-EU_R1206"))
    )
    (comp (ref "R310")
      (value "4.7k")
      (footprint "eagle-import:R1206")
      (libsource (lib "eagle-import") (part "R-EU_R1206"))
    )
    (comp (ref "R311")
      (value "4.7k")
      (footprint "eagle-import:R1206")
      (libsource (lib "eagle-import") (part "R-EU_R1206"))
    )
    (comp (ref "U300")
      (value "IRF7103")
      (footprint "eagle-import:SO8-2")
      (libsource (lib "eagle-import") (part "IRF7103"))
    )
    (comp (ref "C600")
      (value "100n")
      (footprint "eagle-import:C1206K")
      (libsource (lib "eagle-import") (part "C-EUC1206K"))
    )
    (comp (ref "C610")
      (value "22p")
      (footprint "eagle-import:C1206K")
      (libsource (lib "eagle-import") (part "C-EUC1206K"))
    )
    (comp (ref "C611")
      (value "22p")
      (footprint "eagle-import:C1206K")
      (libsource (lib "eagle-import") (part "C-EUC1206K"))
    )
    (comp (ref "Q610")
      (value "32.768kHz")
      (footprint "eagle-import:CM7V-T1A")
      (libsource (lib "eagle-import") (part "QUARZ32.768KHZSMD"))
    )
    (comp (ref "R600")
      (value "10k")
      (footprint "eagle-import:R1206")
      (libsource (lib "eagle-import") (part "R-EU_R1206"))
    )
    (comp (ref "R601")
      (value "10k")
      (footprint "eagle-import:R1206")
      (libsource (lib "eagle-import") (part "R-EU_R1206"))
    )
    (comp (ref "R602")
      (value "DNB")
      (footprint "eagle-import:R1206")
      (libsource (lib "eagle-import") (part "R-EU_R1206"))
    )
    (comp (ref "U600")
      (value "SI473X-D60")
      (footprint "eagle-import:SI473X-D60")
      (libsource (lib "eagle-import") (part "SI473X-D60"))
    )
    (comp (ref "C940")
      (value "100n")
      (footprint "eagle-import:C1206K")
      (libsource (lib "eagle-import") (part "C-EUC1206K"))
    )
    (comp (ref "U940")
      (value "OPT3001")
      (footprint "eagle-import:SON65P200X200X65-7T66X136N")
      (libsource (lib "eagle-import") (part "OPT3001"))
    )
    (comp (ref "X100")
      (value "2510-5")
      (footprint "eagle-import:PAK100_2500-5-10")
      (libsource (lib "eagle-import") (part "2510-5"))
    )
    (comp (ref "X110")
      (value "2510-5")
      (footprint "eagle-import:PAK100_2500-5-10")
      (libsource (lib "eagle-import") (part "2510-5"))
    )
    (comp (ref "C900")
      (value "1u")
      (footprint "eagle-import:C1206K")
      (libsource (lib "eagle-import") (part "C-EUC1206K"))
    )
    (comp (ref "C901")
      (value "100n")
      (footprint "eagle-import:C1206K")
      (libsource (lib "eagle-import") (part "C-EUC1206K"))
    )
    (comp (ref "C903")
      (value "1u")
      (footprint "eagle-import:C1206K")
      (libsource (lib "eagle-import") (part "C-EUC1206K"))
    )
    (comp (ref "C910")
      (value "100n")
      (footprint "eagle-import:C1206K")
      (libsource (lib "eagle-import") (part "C-EUC1206K"))
    )
    (comp (ref "C920")
      (value "100n")
      (footprint "eagle-import:C1206K")
      (libsource (lib "eagle-import") (part "C-EUC1206K"))
    )
    (comp (ref "C930")
      (value "1u")
      (footprint "eagle-import:C1206K")
      (libsource (lib "eagle-import") (part "C-EUC1206K"))
    )
    (comp (ref "J920")
      (value "2060-402")
      (footprint "eagle-import:WAGO_2060-402")
      (fields (field (name "MPN") "2060-402/998-404"))
      (libsource (lib "eagle-import") (part "2060-402"))
    )
    (comp (ref "J921")
      (value "2060-402")
      (footprint "eagle-import:WAGO_2060-402")
      (fields (field (name "MPN") "2060-402/998-404"))
      (libsource (lib "eagle-import") (part "2060-402"))
    )
    (comp (ref "Q900")
      (value "BSS123")
      (footprint "eagle-import:SOT23")
      (libsource (lib "eagle-import") (part "BSS123"))
    )
    (comp (ref "R900")
      (value "4R7")
      (footprint "eagle-import:R1206")
      (libsource (lib "eagle-import") (part "R-EU_R1206"))
    )
    (comp (ref "R901")
      (value "1k")
      (footprint "eagle-import:R1206")
      (libsource (lib "eagle-import") (part "R-EU_R1206"))
    )
    (comp (ref "R921")
      (value "1k")
      (footprint "eagle-import:R1206")
      (libsource (lib "eagle-import") (part "R-EU_R1206"))
    )
    (comp (ref "R922")
      (value "1k")
      (footprint "eagle-import:R1206")
      (libsource (lib "eagle-import") (part "R-EU_R1206"))
    )
    (comp (ref "R923")
      (value "1k")
      (footprint "eagle-import:R1206")
      (libsource (lib "eagle-import") (part "R-EU_R1206"))
    )
    (comp (ref "R930")
      (value "1k")
      (footprint "eagle-import:R1206")
      (libsource (lib "eagle-import") (part "R-EU_R1206"))
    )
    (comp (ref "U900")
      (value "EA_DOGMXXX-A")
      (footprint "eagle-import:EA_DOGMXXX-A")
      (libsource (lib "eagle-import") (part "EA_DOGMXXX-A"))
    )
    (comp (ref "U910")
      (value "PCA8574")
      (footprint "eagle-import:PCA8574_TSSOP16")
      (libsource (lib "eagle-import") (part "PCA8574"))
    )
    (comp (ref "U920")
      (value "PCA9632TK")
      (footprint "eagle-import:TSSOP8")
      (libsource (lib "eagle-import") (part "PCA9632TK"))
    )
    (comp (ref "U930")
      (value "IRF7309")
      (footprint "eagle-import:SO8-2")
      (libsource (lib "eagle-import") (part "IRF7309"))
    )
  )
  (nets
    (net (code "1") (name "+3V3") (class "Default")
      (node (ref "C110") (pin "1") (pinfunction "1_1") (pintype "passive"))
      (node (ref "C200") (pin "1") (pinfunction "1_1") (pintype "passive"))
      (node (ref "C400") (pin "1") (pinfunction "1_1") (pintype "passive"))
      (node (ref "C600") (pin "1") (pinfunction "1_1") (pintype "passive"))
      (node (ref "C940") (pin "1") (pinfunction "1_1") (pintype "passive"))
      (node (ref "CP110") (pin "1") (pinfunction "1_1") (pintype "passive"))
      (node (ref "R200") (pin "2") (pinfunction "2_2") (pintype "passive"))
      (node (ref "R300") (pin "2") (pinfunction "2_2") (pintype "passive"))
      (node (ref "R301") (pin "2") (pinfunction "2_2") (pintype "passive"))
      (node (ref "R600") (pin "2") (pinfunction "2_2") (pintype "passive"))
      (node (ref "R601") (pin "2") (pinfunction "2_2") (pintype "passive"))
      (node (ref "R602") (pin "2") (pinfunction "2_2") (pintype "passive"))
      (node (ref "R801") (pin "2") (pinfunction "2_2") (pintype "passive"))
      (node (ref "R803") (pin "2") (pinfunction "2_2") (pintype "passive"))
      (node (ref "R804") (pin "2") (pinfunction "2_2") (pintype "passive"))
      (node (ref "R811") (pin "1") (pinfunction "1_1") (pintype "passive"))
      (node (ref "R813") (pin "2") (pinfunction "2_2") (pintype "passive"))
      (node (ref "R814") (pin "2") (pinfunction "2_2") (pintype "passive"))
      (node (ref "TP1") (pin "TP") (pinfunction "TP_TP") (pintype "input"))
      (node (ref "TP32") (pin "TP") (pinfunction "TP_TP") (pintype "input"))
      (node (ref "TP33") (pin "TP") (pinfunction "TP_TP") (pintype "input"))
      (node (ref "U100") (pin "4") (pinfunction "VOUT_4") (pintype "bidirectional"))
      (node (ref "U100") (pin "5") (pinfunction "SNS_5") (pintype "bidirectional"))
      (node (ref "U200") (pin "29") (pinfunction "29_29") (pintype "bidirectional"))
      (node (ref "U200") (pin "30") (pinfunction "30_30") (pintype "bidirectional"))
      (node (ref "U300") (pin "2") (pinfunction "G_2") (pintype "bidirectional"))
      (node (ref "U300") (pin "4") (pinfunction "G_4") (pintype "bidirectional"))
      (node (ref "U400") (pin "14") (pinfunction "V+_14") (pintype "power_in"))
      (node (ref "U600") (pin "10") (pinfunction "VD_10") (pintype "bidirectional"))
      (node (ref "U600") (pin "11") (pinfunction "VA_11") (pintype "bidirectional"))
      (node (ref "U940") (pin "1") (pinfunction "VDD_1") (pintype "bidirectional"))
      (node (ref "X110") (pin "10") (pinfunction "KL_10") (pintype "passive"))
    )
    (net (code "2") (name "+5V") (class "Default")
      (node (ref "C100") (pin "1") (pinfunction "1_1") (pintype "passive"))
      (node (ref "C500") (pin "1") (pinfunction "1_1") (pintype "passive"))
      (node (ref "C501") (pin "1") (pinfunction "1_1") (pintype "passive"))
      (node (ref "C900") (pin "1") (pinfunction "1_1") (pintype "passive"))
      (node (ref "C901") (pin "1") (pinfunction "1_1") (pintype "passive"))
      (node (ref "C903") (pin "1") (pinfunction "1_1") (pintype "passive"))
      (node (ref "C930") (pin "1") (pinfunction "1_1") (pintype "passive"))
      (node (ref "CP100") (pin "1") (pinfunction "1_1") (pintype "passive"))
      (node (ref "J921") (pin "B-1") (pinfunction "B-1_B-1") (pintype "passive"))
      (node (ref "R310") (pin "2") (pinfunction "2_2") (pintype "passive"))
      (node (ref "R311") (pin "2") (pinfunction "2_2") (pintype "passive"))
      (node (ref "R930") (pin "2") (pinfunction "2_2") (pintype "passive"))
      (node (ref "TP2") (pin "TP") (pinfunction "TP_TP") (pintype "input"))
      (node (ref "TP29") (pin "TP") (pinfunction "TP_TP") (pintype "input"))
      (node (ref "TP3") (pin "TP") (pinfunction "TP_TP") (pintype "input"))
      (node (ref "TP31") (pin "TP") (pinfunction "TP_TP") (pintype "input"))
      (node (ref "U100") (pin "1") (pinfunction "VIN_1") (pintype "bidirectional"))
      (node (ref "U100") (pin "3") (pinfunction "VEN_3") (pintype "bidirectional"))
      (node (ref "U100") (pin "6") (pinfunction "VIN_6") (pintype "bidirectional"))
      (node (ref "U500") (pin "11") (pinfunction "AVDD_11") (pintype "bidirectional"))
      (node (ref "U500") (pin "12") (pinfunction "AVDD_12") (pintype "bidirectional"))
      (node (ref "U500") (pin "13") (pinfunction "AVDD_13") (pintype "bidirectional"))
      (node (ref "U500") (pin "4") (pinfunction "AVDD_4") (pintype "bidirectional"))
      (node (ref "U500") (pin "5") (pinfunction "AVDD_5") (pintype "bidirectional"))
      (node (ref "U900") (pin "20") (pinfunction "LED2+_20") (pintype "bidirectional"))
      (node (ref "U900") (pin "23") (pinfunction "PSB_23") (pintype "bidirectional"))
      (node (ref "U900") (pin "24") (pinfunction "VOUT_24") (pintype "bidirectional"))
      (node (ref "U900") (pin "25") (pinfunction "VIN_25") (pintype "bidirectional"))
      (node (ref "U900") (pin "26") (pinfunction "VDD_26") (pintype "bidirectional"))
      (node (ref "U900") (pin "32") (pinfunction "D3_32") (pintype "bidirectional"))
      (node (ref "U900") (pin "33") (pinfunction "D2_33") (pintype "bidirectional"))
      (node (ref "U900") (pin "34") (pinfunction "D1_34") (pintype "bidirectional"))
      (node (ref "U900") (pin "35") (pinfunction "D0_35") (pintype "bidirectional"))
      (node (ref "U900") (pin "40") (pinfunction "RESET_40") (pintype "bidirectional"))
      (node (ref "U930") (pin "3") (pinfunction "S_3") (pintype "bidirectional"))
      (node (ref "X110") (pin "9") (pinfunction "KL_9") (pintype "passive"))
    )
    (net (code "3") (name "+5_PCA") (class "Default")
      (node (ref "C910") (pin "1") (pinfunction "1_1") (pintype "passive"))
      (node (ref "C920") (pin "1") (pinfunction "1_1") (pintype "passive"))
      (node (ref "U910") (pin "16") (pinfunction "VDD_16") (pintype "bidirectional"))
      (node (ref "U920") (pin "8") (pinfunction "VDD_8") (pintype "power_in"))
      (node (ref "U930") (pin "5") (pinfunction "D_5") (pintype "bidirectional"))
      (node (ref "U930") (pin "6") (pinfunction "D_6") (pintype "bidirectional"))
    )
    (net (code "4") (name "AMP_GND") (class "Default")
      (node (ref "CP501") (pin "2") (pinfunction "2_2") (pintype "passive"))
      (node (ref "CP503") (pin "2") (pinfunction "2_2") (pintype "passive"))
      (node (ref "JP401") (pin "2") (pinfunction "2_2") (pintype "passive"))
      (node (ref "U400") (pin "12") (pinfunction "COM4_12") (pintype "bidirectional"))
      (node (ref "U400") (pin "8") (pinfunction "COM3_8") (pintype "bidirectional"))
    )
    (net (code "5") (name "AMP_LIN") (class "Default")
      (node (ref "CP500") (pin "2") (pinfunction "2_2") (pintype "passive"))
      (node (ref "TP16") (pin "TP") (pinfunction "TP_TP") (pintype "input"))
      (node (ref "U400") (pin "16") (pinfunction "COM1_16") (pintype "bidirectional"))
    )
    (net (code "6") (name "AMP_OUTL+") (class "Default")
      (node (ref "C510") (pin "2") (pinfunction "2_2") (pintype "passive"))
      (node (ref "J500") (pin "B-1") (pinfunction "B-1_B-1") (pintype "passive"))
      (node (ref "L510") (pin "1") (pinfunction "1_1") (pintype "passive"))
      (node (ref "TP25") (pin "TP") (pinfunction "TP_TP") (pintype "input"))
    )
    (net (code "7") (name "AMP_OUTL-") (class "Default")
      (node (ref "C511") (pin "2") (pinfunction "2_2") (pintype "passive"))
      (node (ref "J500") (pin "B-2") (pinfunction "B-2_B-2") (pintype "passive"))
      (node (ref "L511") (pin "1") (pinfunction "1_1") (pintype "passive"))
      (node (ref "TP26") (pin "TP") (pinfunction "TP_TP") (pintype "input"))
    )
    (net (code "8") (name "AMP_OUTR+") (class "Default")
      (node (ref "C512") (pin "1") (pinfunction "1_1") (pintype "passive"))
      (node (ref "J501") (pin "B-2") (pinfunction "B-2_B-2") (pintype "passive"))
      (node (ref "L512") (pin "1") (pinfunction "1_1") (pintype "passive"))
      (node (ref "TP23") (pin "TP") (pinfunction "TP_TP") (pintype "input"))
    )
    (net (code "9") (name "AMP_OUTR-") (class "Default")
      (node (ref "C513") (pin "1") (pinfunction "1_1") (pintype "passive"))
      (node (ref "J501") (pin "B-1") (pinfunction "B-1_B-1") (pintype "passive"))
      (node (ref "L513") (pin "1") (pinfunction "1_1") (pintype "passive"))
      (node (ref "TP24") (pin "TP") (pinfunction "TP_TP") (pintype "input"))
    )
    (net (code "10") (name "AMP_RIN") (class "Default")
      (node (ref "CP502") (pin "2") (pinfunction "2_2") (pintype "passive"))
      (node (ref "TP17") (pin "TP") (pinfunction "TP_TP") (pintype "input"))
      (node (ref "U400") (pin "4") (pinfunction "COM2_4") (pintype "bidirectional"))
    )
    (net (code "11") (name "AMP_SHUTDOWN") (class "Default")
      (node (ref "U200") (pin "20") (pinfunction "20_20") (pintype "bidirectional"))
      (node (ref "U500") (pin "18") (pinfunction "SDZ_18") (pintype "bidirectional"))
    )
    (net (code "12") (name "ANT_FM") (class "Default")
      (node (ref "ANT") (pin "2") (pinfunction "2_2") (pintype "passive"))
      (node (ref "C650") (pin "1") (pinfunction "1_1") (pintype "passive"))
      (node (ref "TP13") (pin "TP") (pinfunction "TP_TP") (pintype "input"))
    )
    (net (code "13") (name "ANT_LF") (class "Default")
      (node (ref "R651") (pin "1") (pinfunction "1_1") (pintype "passive"))
      (node (ref "U200") (pin "19") (pinfunction "19_19") (pintype "bidirectional"))
    )
    (net (code "14") (name "ANT_MF") (class "Default")
      (node (ref "R650") (pin "1") (pinfunction "1_1") (pintype "passive"))
      (node (ref "U200") (pin "18") (pinfunction "18_18") (pintype "bidirectional"))
    )
    (net (code "15") (name "AUDIO_SW_GND") (class "Default")
      (node (ref "U200") (pin "12") (pinfunction "12_12") (pintype "bidirectional"))
      (node (ref "U400") (pin "10") (pinfunction "IN3-4_10") (pintype "input"))
    )
    (net (code "16") (name "AUDIO_SW_LINE") (class "Default")
      (node (ref "U200") (pin "13") (pinfunction "13_13") (pintype "bidirectional"))
      (node (ref "U400") (pin "2") (pinfunction "IN1-2_2") (pintype "input"))
    )
    (net (code "17") (name "AUX_GND") (class "Default")
      (node (ref "JP400") (pin "1") (pinfunction "1_1") (pintype "passive"))
      (node (ref "TP35") (pin "TP") (pinfunction "TP_TP") (pintype "input"))
      (node (ref "U400") (pin "11") (pinfunction "NO4_11") (pintype "bidirectional"))
      (node (ref "U400") (pin "7") (pinfunction "NO3_7") (pintype "bidirectional"))
      (node (ref "X100") (pin "2") (pinfunction "KL_2") (pintype "passive"))
    )
    (net (code "18") (name "AUX_LIN") (class "Default")
      (node (ref "TP14") (pin "TP") (pinfunction "TP_TP") (pintype "input"))
      (node (ref "U400") (pin "15") (pinfunction "NO1_15") (pintype "bidirectional"))
      (node (ref "X100") (pin "3") (pinfunction "KL_3") (pintype "passive"))
    )
    (net (code "19") (name "AUX_RIN") (class "Default")
      (node (ref "TP15") (pin "TP") (pinfunction "TP_TP") (pintype "input"))
      (node (ref "U400") (pin "3") (pinfunction "NO2_3") (pintype "bidirectional"))
      (node (ref "X100") (pin "1") (pinfunction "KL_1") (pintype "passive"))
    )
    (net (code "20") (name "EN1_A") (class "Default")
      (node (ref "C801") (pin "1") (pinfunction "1_1") (pintype "passive"))
      (node (ref "R802") (pin "2") (pinfunction "2_2") (pintype "passive"))
      (node (ref "U200") (pin "3") (pinfunction "3_3") (pintype "bidirectional"))
    )
    (net (code "21") (name "EN1_B") (class "Default")
      (node (ref "C802") (pin "1") (pinfunction "1_1") (pintype "passive"))
      (node (ref "R805") (pin "2") (pinfunction "2_2") (pintype "passive"))
      (node (ref "U200") (pin "4") (pinfunction "4_4") (pintype "bidirectional"))
    )
    (net (code "22") (name "EN1_TAST") (class "Default")
      (node (ref "C800") (pin "2") (pinfunction "2_2") (pintype "passive"))
      (node (ref "R800") (pin "1") (pinfunction "1_1") (pintype "passive"))
      (node (ref "U200") (pin "5") (pinfunction "5_5") (pintype "bidirectional"))
    )
    (net (code "23") (name "EN2_A") (class "Default")
      (node (ref "C811") (pin "1") (pinfunction "1_1") (pintype "passive"))
      (node (ref "R812") (pin "2") (pinfunction "2_2") (pintype "passive"))
      (node (ref "U200") (pin "9") (pinfunction "9_9") (pintype "bidirectional"))
    )
    (net (code "24") (name "EN2_B") (class "Default")
      (node (ref "C812") (pin "1") (pinfunction "1_1") (pintype "passive"))
      (node (ref "R815") (pin "2") (pinfunction "2_2") (pintype "passive"))
      (node (ref "U200") (pin "10") (pinfunction "10_10") (pintype "bidirectional"))
    )
    (net (code "25") (name "EN2_TAST") (class "Default")
      (node (ref "C810") (pin "1") (pinfunction "1_1") (pintype "passive"))
      (node (ref "R810") (pin "2") (pinfunction "2_2") (pintype "passive"))
      (node (ref "U200") (pin "11") (pinfunction "11_11") (pintype "bidirectional"))
    )
    (net (code "26") (name "GND") (class "Default")
      (node (ref "ANT") (pin "1") (pinfunction "1_1") (pintype "passive"))
      (node (ref "C100") (pin "2") (pinfunction "2_2") (pintype "passive"))
      (node (ref "C110") (pin "2") (pinfunction "2_2") (pintype "passive"))
      (node (ref "C200") (pin "2") (pinfunction "2_2") (pintype "passive"))
      (node (ref "C210") (pin "2") (pinfunction "2_2") (pintype "passive"))
      (node (ref "C211") (pin "2") (pinfunction "2_2") (pintype "passive"))
      (node (ref "C400") (pin "2") (pinfunction "2_2") (pintype "passive"))
      (node (ref "C500") (pin "2") (pinfunction "2_2") (pintype "passive"))
      (node (ref "C501") (pin "2") (pinfunction "2_2") (pintype "passive"))
      (node (ref "C510") (pin "1") (pinfunction "1_1") (pintype "passive"))
      (node (ref "C511") (pin "1") (pinfunction "1_1") (pintype "passive"))
      (node (ref "C512") (pin "2") (pinfunction "2_2") (pintype "passive"))
      (node (ref "C513") (pin "2") (pinfunction "2_2") (pintype "passive"))
      (node (ref "C600") (pin "2") (pinfunction "2_2") (pintype "passive"))
      (node (ref "C610") (pin "1") (pinfunction "1_1") (pintype "passive"))
      (node (ref "C611") (pin "2") (pinfunction "2_2") (pintype "passive"))
      (node (ref "C653") (pin "2") (pinfunction "2_2") (pintype "passive"))
      (node (ref "C654") (pin "2") (pinfunction "2_2") (pintype "passive"))
      (node (ref "C800") (pin "1") (pinfunction "1_1") (pintype "passive"))
      (node (ref "C801") (pin "2") (pinfunction "2_2") (pintype "passive"))
      (node (ref "C802") (pin "2") (pinfunction "2_2") (pintype "passive"))
      (node (ref "C810") (pin "2") (pinfunction "2_2") (pintype "passive"))
      (node (ref "C811") (pin "2") (pinfunction "2_2") (pintype "passive"))
      (node (ref "C812") (pin "2") (pinfunction "2_2") (pintype "passive"))
      (node (ref "C900") (pin "2") (pinfunction "2_2") (pintype "passive"))
      (node (ref "C901") (pin "2") (pinfunction "2_2") (pintype "passive"))
      (node (ref "C903") (pin "2") (pinfunction "2_2") (pintype "passive"))
      (node (ref "C910") (pin "2") (pinfunction "2_2") (pintype "passive"))
      (node (ref "C920") (pin "2") (pinfunction "2_2") (pintype "passive"))
      (node (ref "C930") (pin "2") (pinfunction "2_2") (pintype "passive"))
      (node (ref "C940") (pin "2") (pinfunction "2_2") (pintype "passive"))
      (node (ref "CP100") (pin "2") (pinfunction "2_2") (pintype "passive"))
      (node (ref "CP110") (pin "2") (pinfunction "2_2") (pintype "passive"))
      (node (ref "D650") (pin "1") (pinfunction "A1_1") (pintype "passive"))
      (node (ref "D650") (pin "2") (pinfunction "C2_2") (pintype "passive"))
      (node (ref "EN800") (pin "C") (pinfunction "C_C") (pintype "bidirectional"))
      (node (ref "EN800") (pin "W") (pinfunction "W_W") (pintype "bidirectional"))
      (node (ref "EN810") (pin "C") (pinfunction "C_C") (pintype "bidirectional"))
      (node (ref "EN810") (pin "W") (pinfunction "W_W") (pintype "bidirectional"))
      (node (ref "JP400") (pin "2") (pinfunction "2_2") (pintype "passive"))
      (node (ref "JP401") (pin "1") (pinfunction "1_1") (pintype "passive"))
      (node (ref "JP650") (pin "1") (pinfunction "1_1") (pintype "passive"))
      (node (ref "LF") (pin "2") (pinfunction "2_2") (pintype "passive"))
      (node (ref "Q900") (pin "2") (pinfunction "S_2") (pintype "passive"))
      (node (ref "R901") (pin "1") (pinfunction "1_1") (pintype "passive"))
      (node (ref "TP22") (pin "TP") (pinfunction "TP_TP") (pintype "input"))
      (node (ref "TP30") (pin "TP") (pinfunction "TP_TP") (pintype "input"))
      (node (ref "TP4") (pin "TP") (pinfunction "TP_TP") (pintype "input"))
      (node (ref "TP5") (pin "TP") (pinfunction "TP_TP") (pintype "input"))
      (node (ref "TP6") (pin "TP") (pinfunction "TP_TP") (pintype "input"))
      (node (ref "TP7") (pin "TP") (pinfunction "TP_TP") (pintype "input"))
      (node (ref "TP8") (pin "TP") (pinfunction "TP_TP") (pintype "input"))
      (node (ref "U100") (pin "2") (pinfunction "GND_2") (pintype "bidirectional"))
      (node (ref "U100") (pin "EXP") (pinfunction "EXP_EXP") (pintype "bidirectional"))
      (node (ref "U100") (pin "EXP1") (pinfunction "EXP_EXP1") (pintype "bidirectional"))
      (node (ref "U100") (pin "EXP2") (pinfunction "EXP_EXP2") (pintype "bidirectional"))
      (node (ref "U200") (pin "27") (pinfunction "27_27") (pintype "bidirectional"))
      (node (ref "U200") (pin "28") (pinfunction "28_28") (pintype "bidirectional"))
      (node (ref "U200") (pin "TP") (pinfunction "TP_TP") (pintype "bidirectional"))
      (node (ref "U200") (pin "TP1") (pinfunction "TP_TP1") (pintype "bidirectional"))
      (node (ref "U200") (pin "TP2") (pinfunction "TP_TP2") (pintype "bidirectional"))
      (node (ref "U200") (pin "TP3") (pinfunction "TP_TP3") (pintype "bidirectional"))
      (node (ref "U200") (pin "TP4") (pinfunction "TP_TP4") (pintype "bidirectional"))
      (node (ref "U200") (pin "TP5") (pinfunction "TP_TP5") (pintype "bidirectional"))
      (node (ref "U200") (pin "TP6") (pinfunction "TP_TP6") (pintype "bidirectional"))
      (node (ref "U200") (pin "TP7") (pinfunction "TP_TP7") (pintype "bidirectional"))
      (node (ref "U200") (pin "TP8") (pinfunction "TP_TP8") (pintype "bidirectional"))
      (node (ref "U200") (pin "TP9") (pinfunction "TP_TP9") (pintype "bidirectional"))
      (node (ref "U400") (pin "13") (pinfunction "NC4_13") (pintype "bidirectional"))
      (node (ref "U400") (pin "6") (pinfunction "GND_6") (pintype "power_in"))
      (node (ref "U400") (pin "9") (pinfunction "NC3_9") (pintype "bidirectional"))
      (node (ref "U400") (pin "TH") (pinfunction "GND_TH") (pintype "power_in"))
      (node (ref "U400") (pin "TH1") (pinfunction "GND_TH1") (pintype "power_in"))
      (node (ref "U400") (pin "TH2") (pinfunction "GND_TH2") (pintype "power_in"))
      (node (ref "U400") (pin "TH3") (pinfunction "GND_TH3") (pintype "power_in"))
      (node (ref "U400") (pin "TH4") (pinfunction "GND_TH4") (pintype "power_in"))
      (node (ref "U400") (pin "TH5") (pinfunction "GND_TH5") (pintype "power_in"))
      (node (ref "U500") (pin "3") (pinfunction "AGND_3") (pintype "bidirectional"))
      (node (ref "U500") (pin "8") (pinfunction "PGND_8") (pintype "bidirectional"))
      (node (ref "U500") (pin "EXP") (pinfunction "EXP_EXP") (pintype "bidirectional"))
      (node (ref "U500") (pin "EXP1") (pinfunction "EXP_EXP1") (pintype "bidirectional"))
      (node (ref "U500") (pin "EXP2") (pinfunction "EXP_EXP2") (pintype "bidirectional"))
      (node (ref "U500") (pin "EXP3") (pinfunction "EXP_EXP3") (pintype "bidirectional"))
      (node (ref "U500") (pin "EXP4") (pinfunction "EXP_EXP4") (pintype "bidirectional"))
      (node (ref "U500") (pin "EXP5") (pinfunction "EXP_EXP5") (pintype "bidirectional"))
      (node (ref "U500") (pin "EXP6") (pinfunction "EXP_EXP6") (pintype "bidirectional"))
      (node (ref "U500") (pin "EXP7") (pinfunction "EXP_EXP7") (pintype "bidirectional"))
      (node (ref "U500") (pin "EXP8") (pinfunction "EXP_EXP8") (pintype "bidirectional"))
      (node (ref "U500") (pin "EXP9") (pinfunction "EXP_EXP9") (pintype "bidirectional"))
      (node (ref "U600") (pin "12") (pinfunction "GND_12") (pintype "bidirectional"))
      (node (ref "U600") (pin "3") (pinfunction "RFGND_3") (pintype "bidirectional"))
      (node (ref "U600") (pin "GND-PAD") (pinfunction "GND-PAD_GND-PAD") (pintype "bidirectional"))
      (node (ref "U600") (pin "GND-PAD1") (pinfunction "GND-PAD_GND-PAD1") (pintype "bidirectional"))
      (node (ref "U600") (pin "GND-PAD2") (pinfunction "GND-PAD_GND-PAD2") (pintype "bidirectional"))
      (node (ref "U600") (pin "GND-PAD3") (pinfunction "GND-PAD_GND-PAD3") (pintype "bidirectional"))
      (node (ref "U600") (pin "GND-PAD4") (pinfunction "GND-PAD_GND-PAD4") (pintype "bidirectional"))
      (node (ref "U900") (pin "27") (pinfunction "VSS_27") (pintype "bidirectional"))
      (node (ref "U900") (pin "38") (pinfunction "CS_38") (pintype "bidirectional"))
      (node (ref "U910") (pin "1") (pinfunction "A0_1") (pintype "bidirectional"))
      (node (ref "U910") (pin "2") (pinfunction "A1_2") (pintype "bidirectional"))
      (node (ref "U910") (pin "3") (pinfunction "A2_3") (pintype "bidirectional"))
      (node (ref "U910") (pin "8") (pinfunction "GND_8") (pintype "bidirectional"))
      (node (ref "U920") (pin "5") (pinfunction "VSS_5") (pintype "passive"))
      (node (ref "U930") (pin "1") (pinfunction "S_1") (pintype "bidirectional"))
      (node (ref "U940") (pin "2") (pinfunction "ADDR_2") (pintype "bidirectional"))
      (node (ref "U940") (pin "3") (pinfunction "GND_3") (pintype "bidirectional"))
      (node (ref "U940") (pin "7") (pinfunction "EXP_7") (pintype "bidirectional"))
      (node (ref "X100") (pin "4") (pinfunction "KL_4") (pintype "passive"))
      (node (ref "X100") (pin "6") (pinfunction "KL_6") (pintype "passive"))
      (node (ref "X100") (pin "9") (pinfunction "KL_9") (pintype "passive"))
      (node (ref "X110") (pin "2") (pinfunction "KL_2") (pintype "passive"))
      (node (ref "X110") (pin "4") (pinfunction "KL_4") (pintype "passive"))
      (node (ref "X110") (pin "6") (pinfunction "KL_6") (pintype "passive"))
      (node (ref "X110") (pin "8") (pinfunction "KL_8") (pintype "passive"))
    )
    (net (code "27") (name "LCD_BACKLIGHT") (class "Default")
      (node (ref "Q900") (pin "1") (pinfunction "G_1") (pintype "passive"))
      (node (ref "R901") (pin "2") (pinfunction "2_2") (pintype "passive"))
      (node (ref "TP34") (pin "TP") (pinfunction "TP_TP") (pintype "input"))
      (node (ref "U920") (pin "1") (pinfunction "LED0_1") (pintype "output"))
    )
    (net (code "28") (name "MSP_RESET") (class "Default")
      (node (ref "R200") (pin "1") (pinfunction "1_1") (pintype "passive"))
      (node (ref "TP20") (pin "TP") (pinfunction "TP_TP") (pintype "input"))
      (node (ref "U200") (pin "23") (pinfunction "23_23") (pintype "bidirectional"))
      (node (ref "X110") (pin "7") (pinfunction "KL_7") (pintype "passive"))
    )
    (net (code "29") (name "MSP_RXD") (class "Default")
      (node (ref "TP18") (pin "TP") (pinfunction "TP_TP") (pintype "input"))
      (node (ref "U200") (pin "1") (pinfunction "1_1") (pintype "bidirectional"))
      (node (ref "X110") (pin "3") (pinfunction "KL_3") (pintype "passive"))
    )
    (net (code "30") (name "MSP_TEST") (class "Default")
      (node (ref "TP21") (pin "TP") (pinfunction "TP_TP") (pintype "input"))
      (node (ref "U200") (pin "24") (pinfunction "24_24") (pintype "bidirectional"))
      (node (ref "X110") (pin "5") (pinfunction "KL_5") (pintype "passive"))
    )
    (net (code "31") (name "MSP_TXD") (class "Default")
      (node (ref "TP19") (pin "TP") (pinfunction "TP_TP") (pintype "input"))
      (node (ref "U200") (pin "2") (pinfunction "2_2") (pintype "bidirectional"))
      (node (ref "X110") (pin "1") (pinfunction "KL_1") (pintype "passive"))
    )
    (net (code "32") (name "MSP_XIN") (class "Default")
      (node (ref "C211") (pin "1") (pinfunction "1_1") (pintype "passive"))
      (node (ref "Q210") (pin "P$2") (pinfunction "2_P$2") (pintype "bidirectional"))
      (node (ref "U200") (pin "26") (pinfunction "26_26") (pintype "bidirectional"))
    )
    (net (code "33") (name "MSP_XOUT") (class "Default")
      (node (ref "C210") (pin "1") (pinfunction "1_1") (pintype "passive"))
      (node (ref "Q210") (pin "P$1") (pinfunction "1_P$1") (pintype "bidirectional"))
      (node (ref "U200") (pin "25") (pinfunction "25_25") (pintype "bidirectional"))
    )
    (net (code "34") (name "NC") (class "Default")
      (node (ref "U200") (pin "31") (pinfunction "31_31") (pintype "bidirectional"))
    )
    (net (code "35") (name "Net-(C651-Pad1)") (class "Default")
      (node (ref "C651") (pin "1") (pinfunction "1_1") (pintype "passive"))
      (node (ref "C652") (pin "2") (pinfunction "2_2") (pintype "passive"))
      (node (ref "L650") (pin "1") (pinfunction "1_1") (pintype "passive"))
    )
    (net (code "36") (name "Net-(C653-Pad1)") (class "Default")
      (node (ref "C653") (pin "1") (pinfunction "1_1") (pintype "passive"))
      (node (ref "D651") (pin "A") (pinfunction "A_A") (pintype "passive"))
      (node (ref "R650") (pin "2") (pinfunction "2_2") (pintype "passive"))
    )
    (net (code "37") (name "Net-(C654-Pad1)") (class "Default")
      (node (ref "C654") (pin "1") (pinfunction "1_1") (pintype "passive"))
      (node (ref "D652") (pin "A") (pinfunction "A_A") (pintype "passive"))
      (node (ref "R651") (pin "2") (pinfunction "2_2") (pintype "passive"))
    )
    (net (code "38") (name "Net-(C655-Pad2)") (class "Default")
      (node (ref "C655") (pin "2") (pinfunction "2_2") (pintype "passive"))
      (node (ref "JP650") (pin "3") (pinfunction "3_3") (pintype "passive"))
      (node (ref "L651") (pin "2") (pinfunction "2_2") (pintype "passive"))
    )
    (net (code "39") (name "Net-(D650-C1A2)") (class "Default")
      (node (ref "C650") (pin "2") (pinfunction "2_2") (pintype "passive"))
      (node (ref "C651") (pin "2") (pinfunction "2_2") (pintype "passive"))
      (node (ref "D650") (pin "3") (pinfunction "C1A2_3") (pintype "passive"))
    )
    (net (code "40") (name "Net-(D651-PadC)") (class "Default")
      (node (ref "D651") (pin "C") (pinfunction "C_C") (pintype "passive"))
      (node (ref "HF") (pin "1") (pinfunction "1_1") (pintype "passive"))
      (node (ref "L652") (pin "2") (pinfunction "2_2") (pintype "passive"))
    )
    (net (code "41") (name "Net-(D652-PadC)") (class "Default")
      (node (ref "D652") (pin "C") (pinfunction "C_C") (pintype "passive"))
      (node (ref "L653") (pin "2") (pinfunction "2_2") (pintype "passive"))
      (node (ref "MF") (pin "2") (pinfunction "2_2") (pintype "passive"))
    )
    (net (code "42") (name "Net-(EN800-PadA)") (class "Default")
      (node (ref "EN800") (pin "A") (pinfunction "A_A") (pintype "bidirectional"))
      (node (ref "R802") (pin "1") (pinfunction "1_1") (pintype "passive"))
      (node (ref "R803") (pin "1") (pinfunction "1_1") (pintype "passive"))
    )
    (net (code "43") (name "Net-(EN800-PadB)") (class "Default")
      (node (ref "EN800") (pin "B") (pinfunction "B_B") (pintype "bidirectional"))
      (node (ref "R804") (pin "1") (pinfunction "1_1") (pintype "passive"))
      (node (ref "R805") (pin "1") (pinfunction "1_1") (pintype "passive"))
    )
    (net (code "44") (name "Net-(EN800-PadS)") (class "Default")
      (node (ref "EN800") (pin "S") (pinfunction "S_S") (pintype "bidirectional"))
      (node (ref "R800") (pin "2") (pinfunction "2_2") (pintype "passive"))
      (node (ref "R801") (pin "1") (pinfunction "1_1") (pintype "passive"))
    )
    (net (code "45") (name "Net-(EN810-PadA)") (class "Default")
      (node (ref "EN810") (pin "A") (pinfunction "A_A") (pintype "bidirectional"))
      (node (ref "R812") (pin "1") (pinfunction "1_1") (pintype "passive"))
      (node (ref "R813") (pin "1") (pinfunction "1_1") (pintype "passive"))
    )
    (net (code "46") (name "Net-(EN810-PadB)") (class "Default")
      (node (ref "EN810") (pin "B") (pinfunction "B_B") (pintype "bidirectional"))
      (node (ref "R814") (pin "1") (pinfunction "1_1") (pintype "passive"))
      (node (ref "R815") (pin "1") (pinfunction "1_1") (pintype "passive"))
    )
    (net (code "47") (name "Net-(EN810-PadS)") (class "Default")
      (node (ref "EN810") (pin "S") (pinfunction "S_S") (pintype "bidirectional"))
      (node (ref "R810") (pin "1") (pinfunction "1_1") (pintype "passive"))
      (node (ref "R811") (pin "2") (pinfunction "2_2") (pintype "passive"))
    )
    (net (code "48") (name "Net-(HF-Pad2)") (class "Default")
      (node (ref "HF") (pin "2") (pinfunction "2_2") (pintype "passive"))
      (node (ref "L651") (pin "1") (pinfunction "1_1") (pintype "passive"))
    )
    (net (code "49") (name "Net-(J920-PadB-1)") (class "Default")
      (node (ref "J920") (pin "B-1") (pinfunction "B-1_B-1") (pintype "passive"))
      (node (ref "R921") (pin "2") (pinfunction "2_2") (pintype "passive"))
    )
    (net (code "50") (name "Net-(J920-PadB-2)") (class "Default")
      (node (ref "J920") (pin "B-2") (pinfunction "B-2_B-2") (pintype "passive"))
      (node (ref "R922") (pin "2") (pinfunction "2_2") (pintype "passive"))
    )
    (net (code "51") (name "Net-(J921-PadB-2)") (class "Default")
      (node (ref "J921") (pin "B-2") (pinfunction "B-2_B-2") (pintype "passive"))
      (node (ref "R923") (pin "2") (pinfunction "2_2") (pintype "passive"))
    )
    (net (code "52") (name "Net-(JP650-Pad2)") (class "Default")
      (node (ref "JP650") (pin "2") (pinfunction "2_2") (pintype "passive"))
      (node (ref "L650") (pin "2") (pinfunction "2_2") (pintype "passive"))
    )
    (net (code "53") (name "Net-(L652-Pad1)") (class "Default")
      (node (ref "L652") (pin "1") (pinfunction "1_1") (pintype "passive"))
      (node (ref "MF") (pin "1") (pinfunction "1_1") (pintype "passive"))
    )
    (net (code "54") (name "Net-(L653-Pad1)") (class "Default")
      (node (ref "L653") (pin "1") (pinfunction "1_1") (pintype "passive"))
      (node (ref "LF") (pin "1") (pinfunction "1_1") (pintype "passive"))
    )
    (net (code "55") (name "Net-(Q900-D)") (class "Default")
      (node (ref "Q900") (pin "3") (pinfunction "D_3") (pintype "passive"))
      (node (ref "R900") (pin "2") (pinfunction "2_2") (pintype "passive"))
    )
    (net (code "56") (name "Net-(U500-INL+)") (class "Default")
      (node (ref "CP500") (pin "1") (pinfunction "1_1") (pintype "passive"))
      (node (ref "U500") (pin "1") (pinfunction "INL+_1") (pintype "bidirectional"))
    )
    (net (code "57") (name "Net-(U500-INL-)") (class "Default")
      (node (ref "CP501") (pin "1") (pinfunction "1_1") (pintype "passive"))
      (node (ref "U500") (pin "2") (pinfunction "INL-_2") (pintype "bidirectional"))
    )
    (net (code "58") (name "Net-(U500-INR+)") (class "Default")
      (node (ref "CP502") (pin "1") (pinfunction "1_1") (pintype "passive"))
      (node (ref "U500") (pin "15") (pinfunction "INR+_15") (pintype "bidirectional"))
    )
    (net (code "59") (name "Net-(U500-INR-)") (class "Default")
      (node (ref "CP503") (pin "1") (pinfunction "1_1") (pintype "passive"))
      (node (ref "U500") (pin "14") (pinfunction "INR-_14") (pintype "bidirectional"))
    )
    (net (code "60") (name "Net-(U500-OUTL+)") (class "Default")
      (node (ref "L510") (pin "2") (pinfunction "2_2") (pintype "passive"))
      (node (ref "U500") (pin "6") (pinfunction "OUTL+_6") (pintype "bidirectional"))
    )
    (net (code "61") (name "Net-(U500-OUTL-)") (class "Default")
      (node (ref "L511") (pin "2") (pinfunction "2_2") (pintype "passive"))
      (node (ref "U500") (pin "7") (pinfunction "OUTL-_7") (pintype "bidirectional"))
    )
    (net (code "62") (name "Net-(U500-OUTR+)") (class "Default")
      (node (ref "L512") (pin "2") (pinfunction "2_2") (pintype "passive"))
      (node (ref "U500") (pin "10") (pinfunction "OUTR+_10") (pintype "bidirectional"))
    )
    (net (code "63") (name "Net-(U500-OUTR-)") (class "Default")
      (node (ref "L513") (pin "2") (pinfunction "2_2") (pintype "passive"))
      (node (ref "U500") (pin "9") (pinfunction "OUTR-_9") (pintype "bidirectional"))
    )
    (net (code "64") (name "Net-(U900-D4)") (class "Default")
      (node (ref "U900") (pin "31") (pinfunction "D4_31") (pintype "bidirectional"))
      (node (ref "U910") (pin "4") (pinfunction "P0_4") (pintype "bidirectional"))
    )
    (net (code "65") (name "Net-(U900-D5)") (class "Default")
      (node (ref "U900") (pin "30") (pinfunction "D5_30") (pintype "bidirectional"))
      (node (ref "U910") (pin "5") (pinfunction "P1_5") (pintype "bidirectional"))
    )
    (net (code "66") (name "Net-(U900-D6)") (class "Default")
      (node (ref "U900") (pin "29") (pinfunction "D6_29") (pintype "bidirectional"))
      (node (ref "U910") (pin "6") (pinfunction "P2_6") (pintype "bidirectional"))
    )
    (net (code "67") (name "Net-(U900-D7)") (class "Default")
      (node (ref "U900") (pin "28") (pinfunction "D7_28") (pintype "bidirectional"))
      (node (ref "U910") (pin "7") (pinfunction "P3_7") (pintype "bidirectional"))
    )
    (net (code "68") (name "Net-(U900-E)") (class "Default")
      (node (ref "U900") (pin "36") (pinfunction "E_36") (pintype "bidirectional"))
      (node (ref "U910") (pin "9") (pinfunction "P4_9") (pintype "bidirectional"))
    )
    (net (code "69") (name "Net-(U900-LED1+)") (class "Default")
      (node (ref "U900") (pin "1") (pinfunction "LED1+_1") (pintype "bidirectional"))
      (node (ref "U900") (pin "19") (pinfunction "LED2-_19") (pintype "bidirectional"))
    )
    (net (code "70") (name "Net-(U900-LED1-)") (class "Default")
      (node (ref "R900") (pin "1") (pinfunction "1_1") (pintype "passive"))
      (node (ref "U900") (pin "2") (pinfunction "LED1-_2") (pintype "bidirectional"))
    )
    (net (code "71") (name "Net-(U900-RS)") (class "Default")
      (node (ref "U900") (pin "39") (pinfunction "RS_39") (pintype "bidirectional"))
      (node (ref "U910") (pin "11") (pinfunction "P6_11") (pintype "bidirectional"))
    )
    (net (code "72") (name "Net-(U900-R{slash}W)") (class "Default")
      (node (ref "U900") (pin "37") (pinfunction "R/W_37") (pintype "bidirectional"))
      (node (ref "U910") (pin "10") (pinfunction "P5_10") (pintype "bidirectional"))
    )
    (net (code "73") (name "Net-(U920-LED1)") (class "Default")
      (node (ref "R921") (pin "1") (pinfunction "1_1") (pintype "passive"))
      (node (ref "U920") (pin "2") (pinfunction "LED1_2") (pintype "output"))
    )
    (net (code "74") (name "Net-(U920-LED2)") (class "Default")
      (node (ref "R922") (pin "1") (pinfunction "1_1") (pintype "passive"))
      (node (ref "U920") (pin "3") (pinfunction "LED2_3") (pintype "output"))
    )
    (net (code "75") (name "Net-(U920-LED3)") (class "Default")
      (node (ref "R923") (pin "1") (pinfunction "1_1") (pintype "passive"))
      (node (ref "U920") (pin "4") (pinfunction "LED3_4") (pintype "output"))
    )
    (net (code "76") (name "Net-(U930B-G)") (class "Default")
      (node (ref "R930") (pin "1") (pinfunction "1_1") (pintype "passive"))
      (node (ref "U930") (pin "4") (pinfunction "G_4") (pintype "bidirectional"))
      (node (ref "U930") (pin "7") (pinfunction "D_7") (pintype "bidirectional"))
      (node (ref "U930") (pin "8") (pinfunction "D_8") (pintype "bidirectional"))
    )
    (net (code "77") (name "PCA_INT") (class "Default")
      (node (ref "U200") (pin "17") (pinfunction "17_17") (pintype "bidirectional"))
      (node (ref "U910") (pin "13") (pinfunction "INT_13") (pintype "bidirectional"))
    )
    (net (code "78") (name "PCA_ON_OFF") (class "Default")
      (node (ref "U200") (pin "16") (pinfunction "16_16") (pintype "bidirectional"))
      (node (ref "U930") (pin "2") (pinfunction "G_2") (pintype "bidirectional"))
    )
    (net (code "79") (name "SCL_3.3V") (class "Default")
      (node (ref "R301") (pin "1") (pinfunction "1_1") (pintype "passive"))
      (node (ref "TP10") (pin "TP") (pinfunction "TP_TP") (pintype "input"))
      (node (ref "U200") (pin "21") (pinfunction "21_21") (pintype "bidirectional"))
      (node (ref "U300") (pin "1") (pinfunction "S_1") (pintype "bidirectional"))
      (node (ref "U600") (pin "7") (pinfunction "SCLK_7") (pintype "bidirectional"))
      (node (ref "U940") (pin "4") (pinfunction "SCL_4") (pintype "bidirectional"))
      (node (ref "X100") (pin "10") (pinfunction "KL_10") (pintype "passive"))
    )
    (net (code "80") (name "SCL_5V") (class "Default")
      (node (ref "R311") (pin "1") (pinfunction "1_1") (pintype "passive"))
      (node (ref "TP28") (pin "TP") (pinfunction "TP_TP") (pintype "input"))
      (node (ref "U300") (pin "7") (pinfunction "D_7") (pintype "bidirectional"))
      (node (ref "U300") (pin "8") (pinfunction "D_8") (pintype "bidirectional"))
      (node (ref "U500") (pin "17") (pinfunction "SCL_17") (pintype "bidirectional"))
      (node (ref "U910") (pin "14") (pinfunction "SCL_14") (pintype "bidirectional"))
      (node (ref "U920") (pin "6") (pinfunction "SCL_6") (pintype "input"))
      (node (ref "X100") (pin "5") (pinfunction "KL_5") (pintype "passive"))
    )
    (net (code "81") (name "SDA_3.3V") (class "Default")
      (node (ref "R300") (pin "1") (pinfunction "1_1") (pintype "passive"))
      (node (ref "TP9") (pin "TP") (pinfunction "TP_TP") (pintype "input"))
      (node (ref "U200") (pin "22") (pinfunction "22_22") (pintype "bidirectional"))
      (node (ref "U300") (pin "3") (pinfunction "S_3") (pintype "bidirectional"))
      (node (ref "U600") (pin "8") (pinfunction "SDIO_8") (pintype "bidirectional"))
      (node (ref "U940") (pin "6") (pinfunction "SDA_6") (pintype "bidirectional"))
      (node (ref "X100") (pin "8") (pinfunction "KL_8") (pintype "passive"))
    )
    (net (code "82") (name "SDA_5V") (class "Default")
      (node (ref "R310") (pin "1") (pinfunction "1_1") (pintype "passive"))
      (node (ref "TP27") (pin "TP") (pinfunction "TP_TP") (pintype "input"))
      (node (ref "U300") (pin "5") (pinfunction "D_5") (pintype "bidirectional"))
      (node (ref "U300") (pin "6") (pinfunction "D_6") (pintype "bidirectional"))
      (node (ref "U500") (pin "19") (pinfunction "SDA_19") (pintype "bidirectional"))
      (node (ref "U910") (pin "15") (pinfunction "SDA_15") (pintype "bidirectional"))
      (node (ref "U920") (pin "7") (pinfunction "SDA_7") (pintype "bidirectional"))
      (node (ref "X100") (pin "7") (pinfunction "KL_7") (pintype "passive"))
    )
    (net (code "83") (name "SI_AMI") (class "Default")
      (node (ref "C655") (pin "1") (pinfunction "1_1") (pintype "passive"))
      (node (ref "U600") (pin "4") (pinfunction "AMI_4") (pintype "bidirectional"))
    )
    (net (code "84") (name "SI_DFS") (class "Default")
      (node (ref "U600") (pin "16") (pinfunction "DFS_16") (pintype "bidirectional"))
    )
    (net (code "85") (name "SI_DOUT") (class "Default")
      (node (ref "U600") (pin "15") (pinfunction "DOUT_15") (pintype "bidirectional"))
    )
    (net (code "86") (name "SI_FMI") (class "Default")
      (node (ref "C652") (pin "1") (pinfunction "1_1") (pintype "passive"))
      (node (ref "U600") (pin "2") (pinfunction "FMI_2") (pintype "bidirectional"))
    )
    (net (code "87") (name "SI_GPO1") (class "Default")
      (node (ref "R601") (pin "1") (pinfunction "1_1") (pintype "passive"))
      (node (ref "U600") (pin "19") (pinfunction "GPO1_19") (pintype "bidirectional"))
    )
    (net (code "88") (name "SI_GPO3") (class "Default")
      (node (ref "C611") (pin "1") (pinfunction "1_1") (pintype "passive"))
      (node (ref "Q610") (pin "P$2") (pinfunction "2_P$2") (pintype "bidirectional"))
      (node (ref "U600") (pin "17") (pinfunction "GPO3_17") (pintype "bidirectional"))
    )
    (net (code "89") (name "SI_INT") (class "Default")
      (node (ref "R602") (pin "1") (pinfunction "1_1") (pintype "passive"))
      (node (ref "U200") (pin "15") (pinfunction "15_15") (pintype "bidirectional"))
      (node (ref "U600") (pin "18") (pinfunction "GPO2_18") (pintype "bidirectional"))
    )
    (net (code "90") (name "SI_LOUT") (class "Default")
      (node (ref "TP11") (pin "TP") (pinfunction "TP_TP") (pintype "input"))
      (node (ref "U400") (pin "1") (pinfunction "NC1_1") (pintype "bidirectional"))
      (node (ref "U600") (pin "14") (pinfunction "LOUT_14") (pintype "bidirectional"))
    )
    (net (code "91") (name "SI_RCLK") (class "Default")
      (node (ref "C610") (pin "2") (pinfunction "2_2") (pintype "passive"))
      (node (ref "Q610") (pin "P$1") (pinfunction "1_P$1") (pintype "bidirectional"))
      (node (ref "U600") (pin "9") (pinfunction "RCLK_9") (pintype "bidirectional"))
    )
    (net (code "92") (name "SI_ROUT") (class "Default")
      (node (ref "TP12") (pin "TP") (pinfunction "TP_TP") (pintype "input"))
      (node (ref "U400") (pin "5") (pinfunction "NC2_5") (pintype "bidirectional"))
      (node (ref "U600") (pin "13") (pinfunction "ROUT_13") (pintype "bidirectional"))
    )
    (net (code "93") (name "unconnected-(J500--1-Pad1)") (class "Default")
      (node (ref "J500") (pin "1") (pinfunction "-1_1") (pintype "passive"))
    )
    (net (code "94") (name "unconnected-(J500--2-Pad2)") (class "Default")
      (node (ref "J500") (pin "2") (pinfunction "-2_2") (pintype "passive"))
    )
    (net (code "95") (name "unconnected-(J501--1-Pad1)") (class "Default")
      (node (ref "J501") (pin "1") (pinfunction "-1_1") (pintype "passive"))
    )
    (net (code "96") (name "unconnected-(J501--2-Pad2)") (class "Default")
      (node (ref "J501") (pin "2") (pinfunction "-2_2") (pintype "passive"))
    )
    (net (code "97") (name "unconnected-(J920--1-Pad1)") (class "Default")
      (node (ref "J920") (pin "1") (pinfunction "-1_1") (pintype "passive"))
    )
    (net (code "98") (name "unconnected-(J920--2-Pad2)") (class "Default")
      (node (ref "J920") (pin "2") (pinfunction "-2_2") (pintype "passive"))
    )
    (net (code "99") (name "unconnected-(J921--1-Pad1)") (class "Default")
      (node (ref "J921") (pin "1") (pinfunction "-1_1") (pintype "passive"))
    )
    (net (code "100") (name "unconnected-(J921--2-Pad2)") (class "Default")
      (node (ref "J921") (pin "2") (pinfunction "-2_2") (pintype "passive"))
    )
    (net (code "101") (name "unconnected-(U200-Pad8)") (class "Default")
      (node (ref "U200") (pin "8") (pinfunction "8_8") (pintype "bidirectional"))
    )
    (net (code "102") (name "unconnected-(U200-Pad32)") (class "Default")
      (node (ref "U200") (pin "32") (pinfunction "32_32") (pintype "bidirectional"))
    )
    (net (code "103") (name "unconnected-(U600-NC-Pad1)") (class "Default")
      (node (ref "U600") (pin "1") (pinfunction "NC_1") (pintype "bidirectional"))
    )
    (net (code "104") (name "unconnected-(U600-NC.-Pad20)") (class "Default")
      (node (ref "U600") (pin "20") (pinfunction "NC._20") (pintype "bidirectional"))
    )
    (net (code "105") (name "unconnected-(U900-CAP+-Pad22)") (class "Default")
      (node (ref "U900") (pin "22") (pinfunction "CAP+_22") (pintype "bidirectional"))
    )
    (net (code "106") (name "unconnected-(U900-CAP--Pad21)") (class "Default")
      (node (ref "U900") (pin "21") (pinfunction "CAP-_21") (pintype "bidirectional"))
    )
    (net (code "107") (name "unconnected-(U910-P7-Pad12)") (class "Default")
      (node (ref "U910") (pin "12") (pinfunction "P7_12") (pintype "bidirectional"))
    )
    (net (code "108") (name "~{OPT_INT}") (class "Default")
      (node (ref "U200") (pin "14") (pinfunction "14_14") (pintype "bidirectional"))
      (node (ref "U940") (pin "5") (pinfunction "~{INT}_5") (pintype "bidirectional"))
    )
    (net (code "109") (name "~{SI_EN}") (class "Default")
      (node (ref "U200") (pin "7") (pinfunction "7_7") (pintype "bidirectional"))
      (node (ref "U600") (pin "6") (pinfunction "SEN_6") (pintype "bidirectional"))
    )
    (net (code "110") (name "~{SI_RST}") (class "Default")
      (node (ref "R600") (pin "1") (pinfunction "1_1") (pintype "passive"))
      (node (ref "U200") (pin "6") (pinfunction "6_6") (pintype "bidirectional"))
      (node (ref "U600") (pin "5") (pinfunction "RST_5") (pintype "bidirectional"))
    )
  )
)
